# Vorlage_ATmega2560-16AU.net
KiCad netlist of a schematic drawn in EAGLE
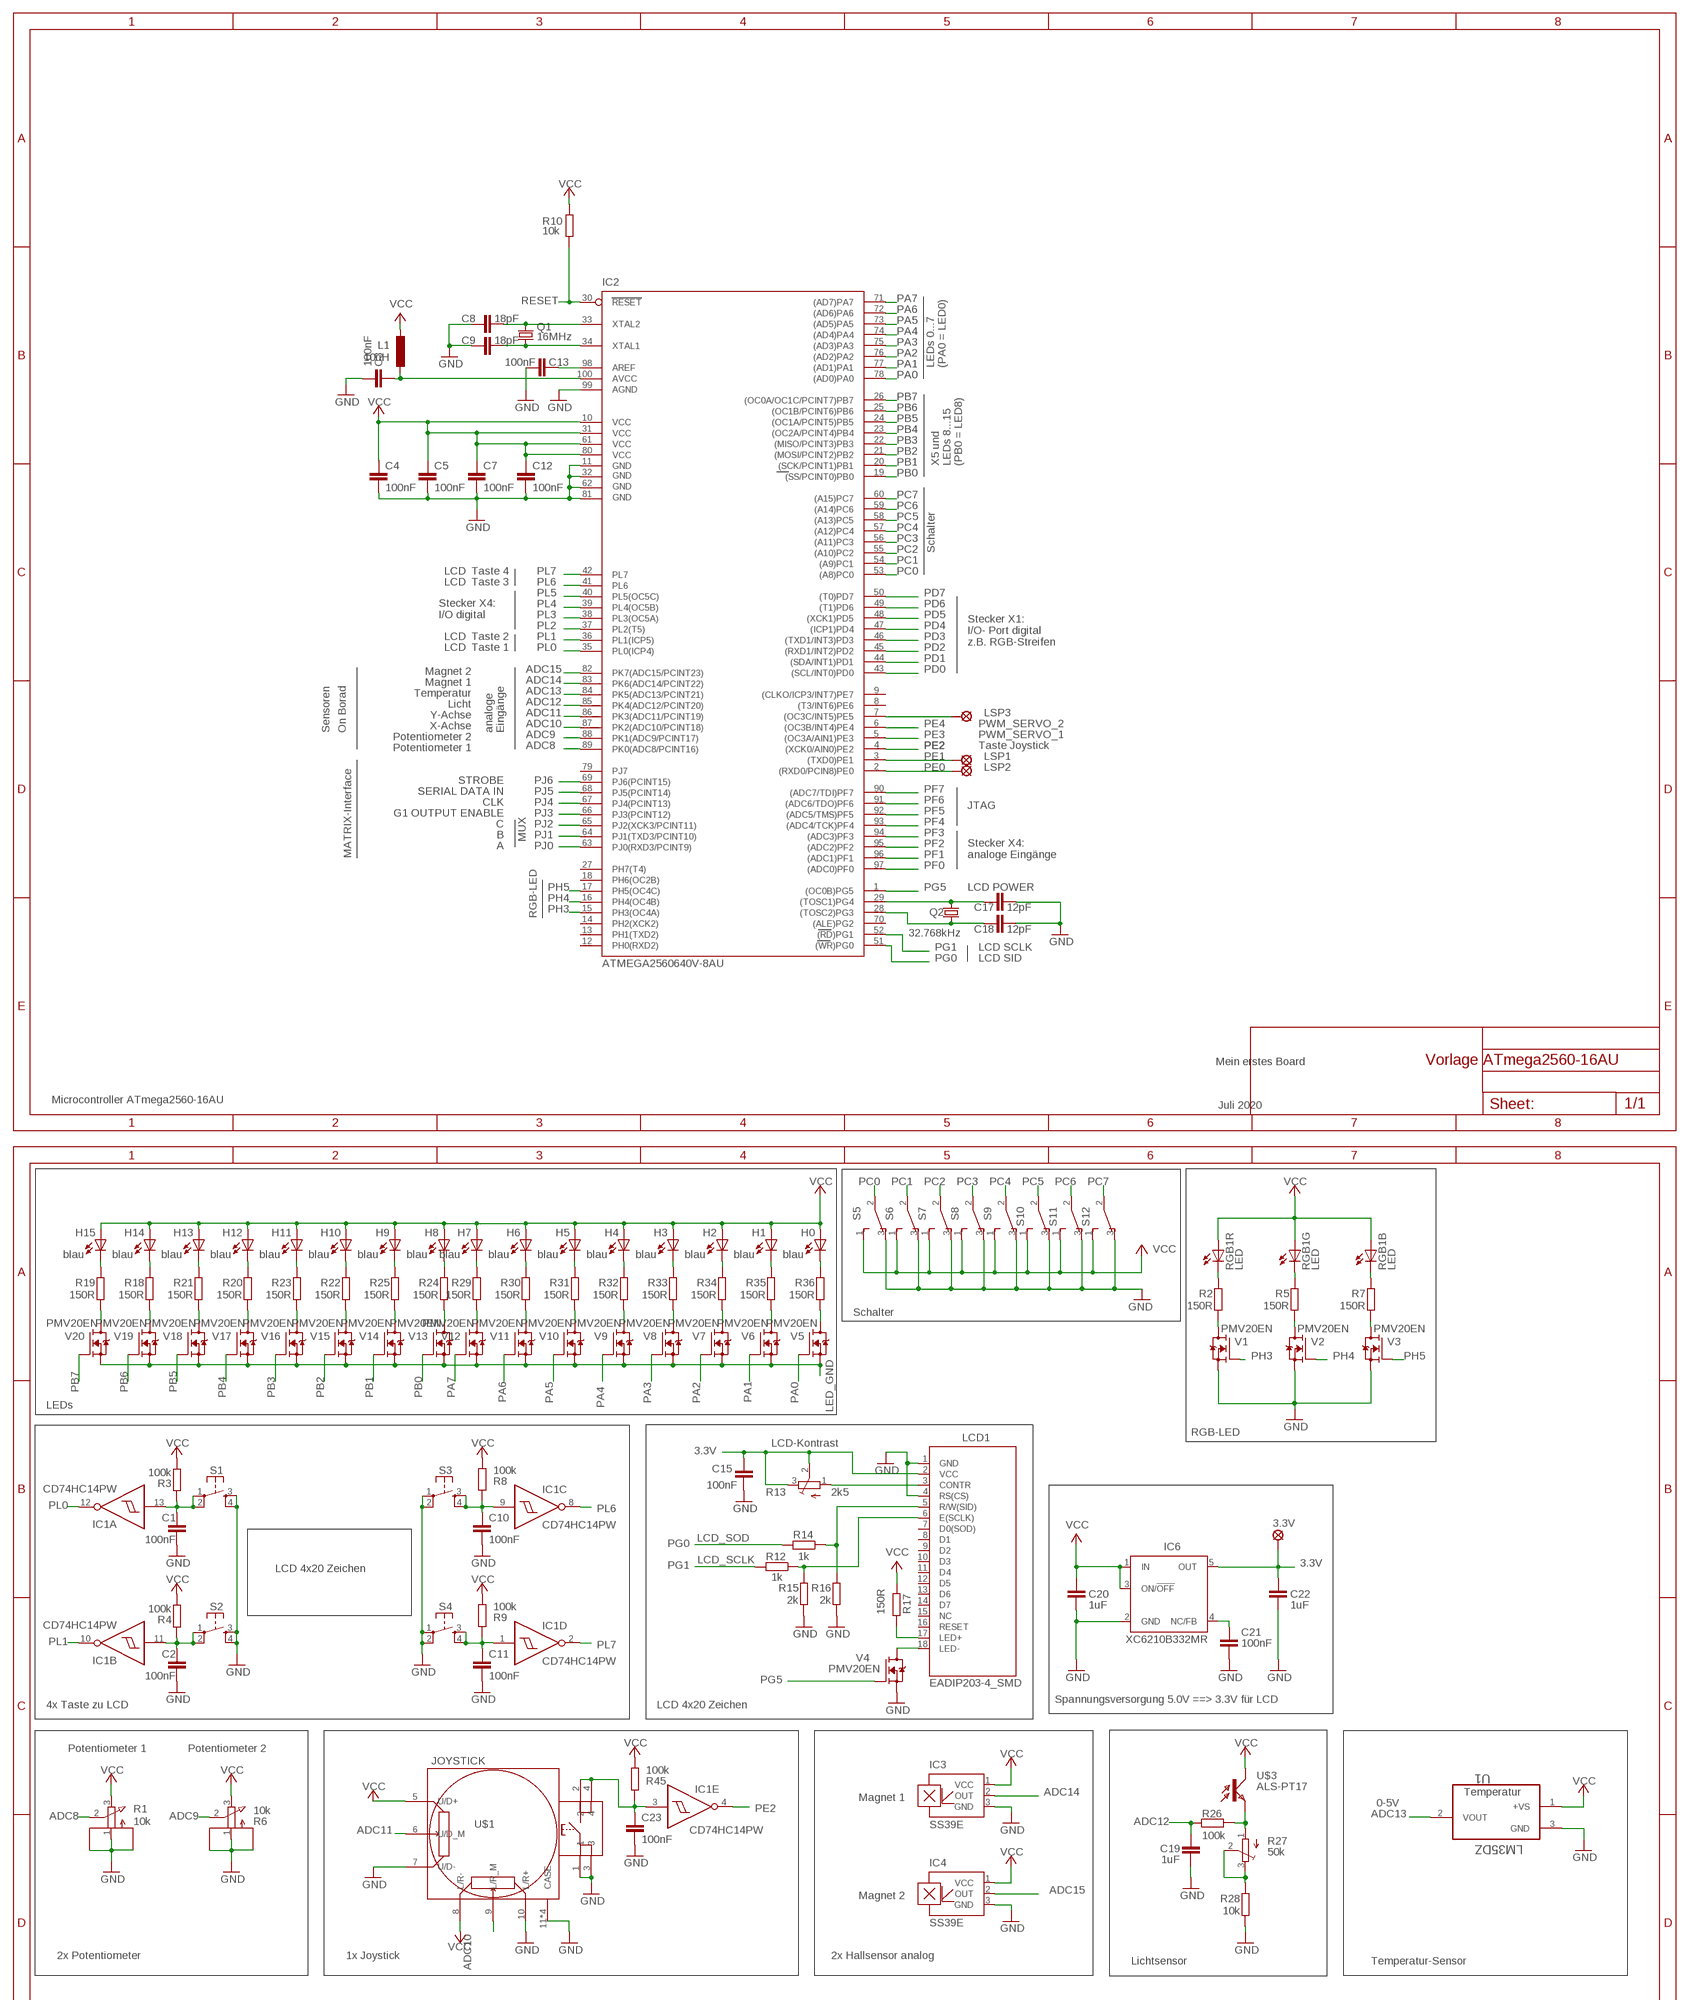
[diagram p0: schematic, sheet 1, part 1 of 2]
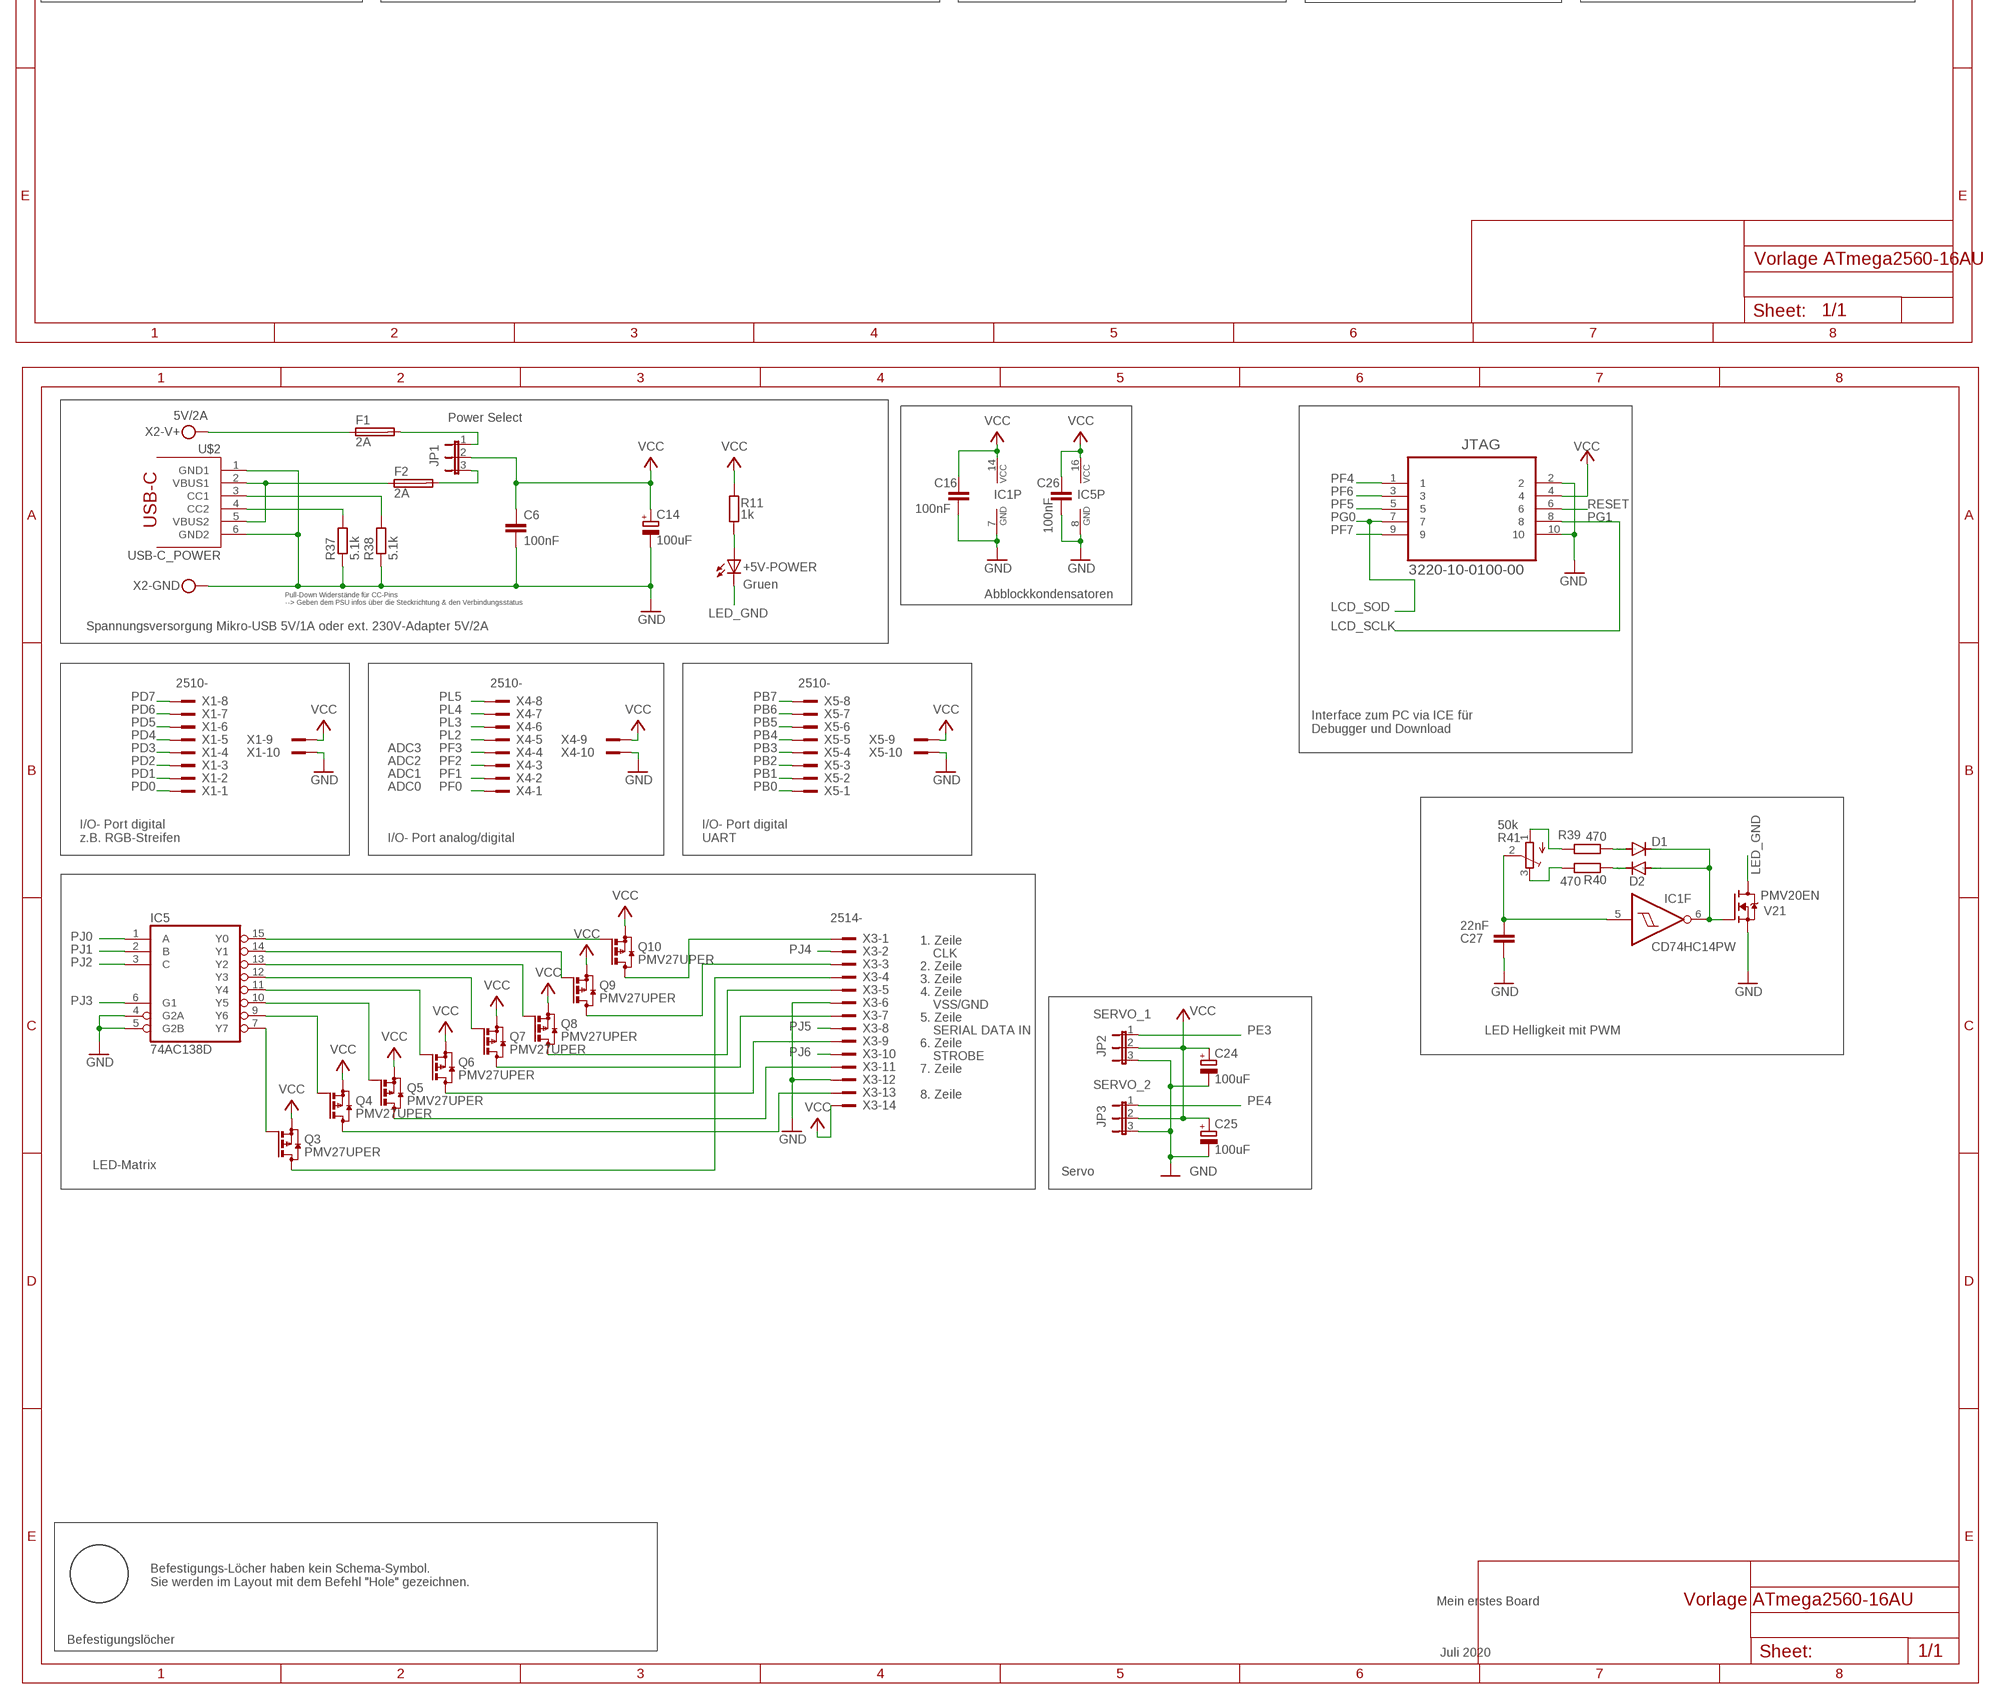
[diagram p1: schematic, sheet 1, part 2 of 2]

(export (version "E")
  (design (tool "Eeschema 10.0.6"))
  (components
    (comp (ref "+5V-POWER")
      (value "Gruen")
      (footprint "eagle-import:CHIPLED_1206")
      (libsource (lib "eagle-import") (part "LEDCHIPLED_1206"))
    )
    (comp (ref "3.3V")
      (value "3.3V")
      (footprint "eagle-import:LSP11")
      (libsource (lib "eagle-import") (part "LSP11"))
    )
    (comp (ref "C1")
      (value "100nF")
      (footprint "eagle-import:C1206")
      (libsource (lib "eagle-import") (part "C-EUC1206"))
    )
    (comp (ref "C2")
      (value "100nF")
      (footprint "eagle-import:C1206")
      (libsource (lib "eagle-import") (part "C-EUC1206"))
    )
    (comp (ref "C3")
      (value "100nF")
      (footprint "eagle-import:C1206")
      (libsource (lib "eagle-import") (part "C-EUC1206"))
    )
    (comp (ref "C4")
      (value "100nF")
      (footprint "eagle-import:C1206")
      (libsource (lib "eagle-import") (part "C-EUC1206"))
    )
    (comp (ref "C5")
      (value "100nF")
      (footprint "eagle-import:C1206")
      (libsource (lib "eagle-import") (part "C-EUC1206"))
    )
    (comp (ref "C6")
      (value "100nF")
      (footprint "eagle-import:C1206")
      (libsource (lib "eagle-import") (part "C-EUC1206"))
    )
    (comp (ref "C7")
      (value "100nF")
      (footprint "eagle-import:C1206")
      (libsource (lib "eagle-import") (part "C-EUC1206"))
    )
    (comp (ref "C8")
      (value "18pF")
      (footprint "eagle-import:C0805K")
      (libsource (lib "eagle-import") (part "C-EUC0805K"))
    )
    (comp (ref "C9")
      (value "18pF")
      (footprint "eagle-import:C0805K")
      (libsource (lib "eagle-import") (part "C-EUC0805K"))
    )
    (comp (ref "C10")
      (value "100nF")
      (footprint "eagle-import:C1206")
      (libsource (lib "eagle-import") (part "C-EUC1206"))
    )
    (comp (ref "C11")
      (value "100nF")
      (footprint "eagle-import:C1206")
      (libsource (lib "eagle-import") (part "C-EUC1206"))
    )
    (comp (ref "C12")
      (value "100nF")
      (footprint "eagle-import:C1206")
      (libsource (lib "eagle-import") (part "C-EUC1206"))
    )
    (comp (ref "C13")
      (value "100nF")
      (footprint "eagle-import:C1206")
      (libsource (lib "eagle-import") (part "C-EUC1206"))
    )
    (comp (ref "C14")
      (value "100uF")
      (footprint "eagle-import:UD-6,3X5,8_NICHICON")
      (libsource (lib "eagle-import") (part "CPOL-EUUD-6,3X8,8"))
    )
    (comp (ref "C15")
      (value "100nF")
      (footprint "eagle-import:C1206")
      (libsource (lib "eagle-import") (part "C-EUC1206"))
    )
    (comp (ref "C16")
      (value "100nF")
      (footprint "eagle-import:C1206")
      (libsource (lib "eagle-import") (part "C-EUC1206"))
    )
    (comp (ref "C17")
      (value "12pF")
      (footprint "eagle-import:C0805K")
      (libsource (lib "eagle-import") (part "C-EUC0805K"))
    )
    (comp (ref "C18")
      (value "12pF")
      (footprint "eagle-import:C0805K")
      (libsource (lib "eagle-import") (part "C-EUC0805K"))
    )
    (comp (ref "C19")
      (value "1uF")
      (footprint "eagle-import:C1206")
      (libsource (lib "eagle-import") (part "C-EUC1206"))
    )
    (comp (ref "C20")
      (value "1uF")
      (footprint "eagle-import:C1206")
      (libsource (lib "eagle-import") (part "C-EUC1206"))
    )
    (comp (ref "C21")
      (value "100nF")
      (footprint "eagle-import:C1206")
      (libsource (lib "eagle-import") (part "C-EUC1206"))
    )
    (comp (ref "C22")
      (value "1uF")
      (footprint "eagle-import:C1206")
      (libsource (lib "eagle-import") (part "C-EUC1206"))
    )
    (comp (ref "C23")
      (value "100nF")
      (footprint "eagle-import:C1206")
      (libsource (lib "eagle-import") (part "C-EUC1206"))
    )
    (comp (ref "C24")
      (value "100uF")
      (footprint "eagle-import:UD-6,3X5,8_NICHICON")
      (libsource (lib "eagle-import") (part "CPOL-EUUD-6,3X8,8"))
    )
    (comp (ref "C25")
      (value "100uF")
      (footprint "eagle-import:UD-6,3X5,8_NICHICON")
      (libsource (lib "eagle-import") (part "CPOL-EUUD-6,3X8,8"))
    )
    (comp (ref "C26")
      (value "100nF")
      (footprint "eagle-import:C1206")
      (libsource (lib "eagle-import") (part "C-EUC1206"))
    )
    (comp (ref "C27")
      (value "22nF")
      (footprint "eagle-import:C0805")
      (libsource (lib "eagle-import") (part "C-EUC0805"))
    )
    (comp (ref "D1")
      (value "DIODE-SOD123")
      (footprint "eagle-import:SOD123")
      (libsource (lib "eagle-import") (part "DIODE-SOD123"))
    )
    (comp (ref "D2")
      (value "DIODE-SOD123")
      (footprint "eagle-import:SOD123")
      (libsource (lib "eagle-import") (part "DIODE-SOD123"))
    )
    (comp (ref "F1")
      (value "2A")
      (footprint "eagle-import:F1206")
      (libsource (lib "eagle-import") (part "195601206"))
    )
    (comp (ref "F2")
      (value "2A")
      (footprint "eagle-import:F1206")
      (libsource (lib "eagle-import") (part "195601206"))
    )
    (comp (ref "H0")
      (value "blau")
      (footprint "eagle-import:CHIPLED_1206")
      (libsource (lib "eagle-import") (part "LEDCHIPLED_1206"))
    )
    (comp (ref "H1")
      (value "blau")
      (footprint "eagle-import:CHIPLED_1206")
      (libsource (lib "eagle-import") (part "LEDCHIPLED_1206"))
    )
    (comp (ref "H2")
      (value "blau")
      (footprint "eagle-import:CHIPLED_1206")
      (libsource (lib "eagle-import") (part "LEDCHIPLED_1206"))
    )
    (comp (ref "H3")
      (value "blau")
      (footprint "eagle-import:CHIPLED_1206")
      (libsource (lib "eagle-import") (part "LEDCHIPLED_1206"))
    )
    (comp (ref "H4")
      (value "blau")
      (footprint "eagle-import:CHIPLED_1206")
      (libsource (lib "eagle-import") (part "LEDCHIPLED_1206"))
    )
    (comp (ref "H5")
      (value "blau")
      (footprint "eagle-import:CHIPLED_1206")
      (libsource (lib "eagle-import") (part "LEDCHIPLED_1206"))
    )
    (comp (ref "H6")
      (value "blau")
      (footprint "eagle-import:CHIPLED_1206")
      (libsource (lib "eagle-import") (part "LEDCHIPLED_1206"))
    )
    (comp (ref "H7")
      (value "blau")
      (footprint "eagle-import:CHIPLED_1206")
      (libsource (lib "eagle-import") (part "LEDCHIPLED_1206"))
    )
    (comp (ref "H8")
      (value "blau")
      (footprint "eagle-import:CHIPLED_1206")
      (libsource (lib "eagle-import") (part "LEDCHIPLED_1206"))
    )
    (comp (ref "H9")
      (value "blau")
      (footprint "eagle-import:CHIPLED_1206")
      (libsource (lib "eagle-import") (part "LEDCHIPLED_1206"))
    )
    (comp (ref "H10")
      (value "blau")
      (footprint "eagle-import:CHIPLED_1206")
      (libsource (lib "eagle-import") (part "LEDCHIPLED_1206"))
    )
    (comp (ref "H11")
      (value "blau")
      (footprint "eagle-import:CHIPLED_1206")
      (libsource (lib "eagle-import") (part "LEDCHIPLED_1206"))
    )
    (comp (ref "H12")
      (value "blau")
      (footprint "eagle-import:CHIPLED_1206")
      (libsource (lib "eagle-import") (part "LEDCHIPLED_1206"))
    )
    (comp (ref "H13")
      (value "blau")
      (footprint "eagle-import:CHIPLED_1206")
      (libsource (lib "eagle-import") (part "LEDCHIPLED_1206"))
    )
    (comp (ref "H14")
      (value "blau")
      (footprint "eagle-import:CHIPLED_1206")
      (libsource (lib "eagle-import") (part "LEDCHIPLED_1206"))
    )
    (comp (ref "H15")
      (value "blau")
      (footprint "eagle-import:CHIPLED_1206")
      (libsource (lib "eagle-import") (part "LEDCHIPLED_1206"))
    )
    (comp (ref "IC1")
      (value "CD74HC14PW")
      (footprint "eagle-import:SO14")
      (libsource (lib "eagle-import") (part "7414D"))
    )
    (comp (ref "IC2")
      (value "ATMEGA2560640V-8AU")
      (footprint "eagle-import:TQFP100")
      (libsource (lib "eagle-import") (part "ATMEGA2560AU640V-8"))
    )
    (comp (ref "IC3")
      (value "SS39E")
      (footprint "eagle-import:SOT23-W")
      (fields (field (name "MF") "ALLEGRO MICROSYSTEMS, INC.") (field (name "MPN") "A1301ELHLT-T"))
      (libsource (lib "eagle-import") (part "A13?LH01"))
    )
    (comp (ref "IC4")
      (value "SS39E")
      (footprint "eagle-import:SOT23-W")
      (fields (field (name "MF") "ALLEGRO MICROSYSTEMS, INC.") (field (name "MPN") "A1301ELHLT-T"))
      (libsource (lib "eagle-import") (part "A13?LH01"))
    )
    (comp (ref "IC5")
      (value "74AC138D")
      (footprint "eagle-import:SO16")
      (libsource (lib "eagle-import") (part "74138DAC"))
    )
    (comp (ref "IC6")
      (value "XC6210B332MR")
      (footprint "eagle-import:SOT23-DBV")
      (libsource (lib "eagle-import") (part "LP2985-XXDBVR"))
    )
    (comp (ref "JP1")
      (value "Power Select")
      (footprint "eagle-import:JP2")
      (libsource (lib "eagle-import") (part "JP2E"))
    )
    (comp (ref "JP2")
      (value "SERVO_1")
      (footprint "eagle-import:JP2")
      (libsource (lib "eagle-import") (part "JP2E"))
    )
    (comp (ref "JP3")
      (value "SERVO_2")
      (footprint "eagle-import:JP2")
      (libsource (lib "eagle-import") (part "JP2E"))
    )
    (comp (ref "JTAG")
      (value "3220-10-0100-00")
      (footprint "eagle-import:SAMTEC_FTS-105-01-L-D")
      (fields (field (name "MPN") "FTS-105-01-L-D"))
      (libsource (lib "eagle-import") (part "FTS-105-01-L-D"))
    )
    (comp (ref "L1")
      (value "10uH")
      (footprint "eagle-import:L2825P")
      (libsource (lib "eagle-import") (part "L-EUL2825P"))
    )
    (comp (ref "LCD1")
      (value "EADIP203-4_SMD")
      (footprint "eagle-import:EADIP203-4SMD")
      (libsource (lib "eagle-import") (part "EADIP203-4EADIP203-4SMD"))
    )
    (comp (ref "LSP1")
      (value "LSP11")
      (footprint "eagle-import:LSP11")
      (libsource (lib "eagle-import") (part "LSP11"))
    )
    (comp (ref "LSP2")
      (value "LSP11")
      (footprint "eagle-import:LSP11")
      (libsource (lib "eagle-import") (part "LSP11"))
    )
    (comp (ref "LSP3")
      (value "LSP11")
      (footprint "eagle-import:LSP11")
      (libsource (lib "eagle-import") (part "LSP11"))
    )
    (comp (ref "Q1")
      (value "16MHz")
      (footprint "eagle-import:HC49UP")
      (libsource (lib "eagle-import") (part "CRYSTALHC49UP"))
    )
    (comp (ref "Q2")
      (value "32.768kHz")
      (footprint "eagle-import:TC38H")
      (libsource (lib "eagle-import") (part "CRYSTALTC38H"))
    )
    (comp (ref "Q3")
      (value "PMV27UPER")
      (footprint "eagle-import:SOT23")
      (libsource (lib "eagle-import") (part "BSS84"))
    )
    (comp (ref "Q4")
      (value "PMV27UPER")
      (footprint "eagle-import:SOT23")
      (libsource (lib "eagle-import") (part "BSS84"))
    )
    (comp (ref "Q5")
      (value "PMV27UPER")
      (footprint "eagle-import:SOT23")
      (libsource (lib "eagle-import") (part "BSS84"))
    )
    (comp (ref "Q6")
      (value "PMV27UPER")
      (footprint "eagle-import:SOT23")
      (libsource (lib "eagle-import") (part "BSS84"))
    )
    (comp (ref "Q7")
      (value "PMV27UPER")
      (footprint "eagle-import:SOT23")
      (libsource (lib "eagle-import") (part "BSS84"))
    )
    (comp (ref "Q8")
      (value "PMV27UPER")
      (footprint "eagle-import:SOT23")
      (libsource (lib "eagle-import") (part "BSS84"))
    )
    (comp (ref "Q9")
      (value "PMV27UPER")
      (footprint "eagle-import:SOT23")
      (libsource (lib "eagle-import") (part "BSS84"))
    )
    (comp (ref "Q10")
      (value "PMV27UPER")
      (footprint "eagle-import:SOT23")
      (libsource (lib "eagle-import") (part "BSS84"))
    )
    (comp (ref "R1")
      (value "10k")
      (footprint "eagle-import:EVUF")
      (libsource (lib "eagle-import") (part "EVUA"))
    )
    (comp (ref "R2")
      (value "150R")
      (footprint "eagle-import:R1206")
      (libsource (lib "eagle-import") (part "rcl_334_R-EU_R1206"))
    )
    (comp (ref "R3")
      (value "100k")
      (footprint "eagle-import:R1206")
      (libsource (lib "eagle-import") (part "rcl_334_R-EU_R1206"))
    )
    (comp (ref "R4")
      (value "100k")
      (footprint "eagle-import:R1206")
      (libsource (lib "eagle-import") (part "rcl_334_R-EU_R1206"))
    )
    (comp (ref "R5")
      (value "150R")
      (footprint "eagle-import:R1206")
      (libsource (lib "eagle-import") (part "rcl_334_R-EU_R1206"))
    )
    (comp (ref "R6")
      (value "10k")
      (footprint "eagle-import:EVUF")
      (libsource (lib "eagle-import") (part "EVUA"))
    )
    (comp (ref "R7")
      (value "150R")
      (footprint "eagle-import:R1206")
      (libsource (lib "eagle-import") (part "rcl_334_R-EU_R1206"))
    )
    (comp (ref "R8")
      (value "100k")
      (footprint "eagle-import:R1206")
      (libsource (lib "eagle-import") (part "rcl_334_R-EU_R1206"))
    )
    (comp (ref "R9")
      (value "100k")
      (footprint "eagle-import:R1206")
      (libsource (lib "eagle-import") (part "rcl_334_R-EU_R1206"))
    )
    (comp (ref "R10")
      (value "10k")
      (footprint "eagle-import:R1206")
      (libsource (lib "eagle-import") (part "rcl_334_R-EU_R1206"))
    )
    (comp (ref "R11")
      (value "1k")
      (footprint "eagle-import:R1206")
      (libsource (lib "eagle-import") (part "rcl_334_R-EU_R1206"))
    )
    (comp (ref "R12")
      (value "1k")
      (footprint "eagle-import:R1206")
      (libsource (lib "eagle-import") (part "rcl_334_R-EU_R1206"))
    )
    (comp (ref "R13")
      (value "2k5")
      (footprint "eagle-import:3223G")
      (libsource (lib "eagle-import") (part "TRIM_EU-3223G"))
    )
    (comp (ref "R14")
      (value "1k")
      (footprint "eagle-import:R1206")
      (libsource (lib "eagle-import") (part "rcl_334_R-EU_R1206"))
    )
    (comp (ref "R15")
      (value "2k")
      (footprint "eagle-import:R1206")
      (libsource (lib "eagle-import") (part "rcl_334_R-EU_R1206"))
    )
    (comp (ref "R16")
      (value "2k")
      (footprint "eagle-import:R1206")
      (libsource (lib "eagle-import") (part "rcl_334_R-EU_R1206"))
    )
    (comp (ref "R17")
      (value "150R")
      (footprint "eagle-import:R1206")
      (libsource (lib "eagle-import") (part "rcl_334_R-EU_R1206"))
    )
    (comp (ref "R18")
      (value "150R")
      (footprint "eagle-import:R1206")
      (libsource (lib "eagle-import") (part "rcl_334_R-EU_R1206"))
    )
    (comp (ref "R19")
      (value "150R")
      (footprint "eagle-import:R1206")
      (libsource (lib "eagle-import") (part "rcl_334_R-EU_R1206"))
    )
    (comp (ref "R20")
      (value "150R")
      (footprint "eagle-import:R1206")
      (libsource (lib "eagle-import") (part "rcl_334_R-EU_R1206"))
    )
    (comp (ref "R21")
      (value "150R")
      (footprint "eagle-import:R1206")
      (libsource (lib "eagle-import") (part "rcl_334_R-EU_R1206"))
    )
    (comp (ref "R22")
      (value "150R")
      (footprint "eagle-import:R1206")
      (libsource (lib "eagle-import") (part "rcl_334_R-EU_R1206"))
    )
    (comp (ref "R23")
      (value "150R")
      (footprint "eagle-import:R1206")
      (libsource (lib "eagle-import") (part "rcl_334_R-EU_R1206"))
    )
    (comp (ref "R24")
      (value "150R")
      (footprint "eagle-import:R1206")
      (libsource (lib "eagle-import") (part "rcl_334_R-EU_R1206"))
    )
    (comp (ref "R25")
      (value "150R")
      (footprint "eagle-import:R1206")
      (libsource (lib "eagle-import") (part "rcl_334_R-EU_R1206"))
    )
    (comp (ref "R26")
      (value "100k")
      (footprint "eagle-import:R1206")
      (libsource (lib "eagle-import") (part "rcl_334_R-EU_R1206"))
    )
    (comp (ref "R27")
      (value "50k")
      (footprint "eagle-import:3223G")
      (libsource (lib "eagle-import") (part "TRIM_EU-3223G"))
    )
    (comp (ref "R28")
      (value "10k")
      (footprint "eagle-import:R1206")
      (libsource (lib "eagle-import") (part "rcl_334_R-EU_R1206"))
    )
    (comp (ref "R29")
      (value "150R")
      (footprint "eagle-import:R1206")
      (libsource (lib "eagle-import") (part "rcl_334_R-EU_R1206"))
    )
    (comp (ref "R30")
      (value "150R")
      (footprint "eagle-import:R1206")
      (libsource (lib "eagle-import") (part "rcl_334_R-EU_R1206"))
    )
    (comp (ref "R31")
      (value "150R")
      (footprint "eagle-import:R1206")
      (libsource (lib "eagle-import") (part "rcl_334_R-EU_R1206"))
    )
    (comp (ref "R32")
      (value "150R")
      (footprint "eagle-import:R1206")
      (libsource (lib "eagle-import") (part "rcl_334_R-EU_R1206"))
    )
    (comp (ref "R33")
      (value "150R")
      (footprint "eagle-import:R1206")
      (libsource (lib "eagle-import") (part "rcl_334_R-EU_R1206"))
    )
    (comp (ref "R34")
      (value "150R")
      (footprint "eagle-import:R1206")
      (libsource (lib "eagle-import") (part "rcl_334_R-EU_R1206"))
    )
    (comp (ref "R35")
      (value "150R")
      (footprint "eagle-import:R1206")
      (libsource (lib "eagle-import") (part "rcl_334_R-EU_R1206"))
    )
    (comp (ref "R36")
      (value "150R")
      (footprint "eagle-import:R1206")
      (libsource (lib "eagle-import") (part "rcl_334_R-EU_R1206"))
    )
    (comp (ref "R37")
      (value "5.1k")
      (footprint "eagle-import:R0805")
      (libsource (lib "eagle-import") (part "R-EU_R0805"))
    )
    (comp (ref "R38")
      (value "5.1k")
      (footprint "eagle-import:R0805")
      (libsource (lib "eagle-import") (part "R-EU_R0805"))
    )
    (comp (ref "R39")
      (value "470")
      (footprint "eagle-import:R0805")
      (libsource (lib "eagle-import") (part "R-EU_R0805"))
    )
    (comp (ref "R40")
      (value "470")
      (footprint "eagle-import:R0805")
      (libsource (lib "eagle-import") (part "R-EU_R0805"))
    )
    (comp (ref "R41")
      (value "50k")
      (footprint "eagle-import:3223G")
      (libsource (lib "eagle-import") (part "TRIM_EU-3223G"))
    )
    (comp (ref "R45")
      (value "100k")
      (footprint "eagle-import:R1206")
      (libsource (lib "eagle-import") (part "rcl_334_R-EU_R1206"))
    )
    (comp (ref "RGB1")
      (value "LED")
      (footprint "eagle-import:LED_MIT_DIFUSOR")
      (libsource (lib "eagle-import") (part "GM5WA94310AMIT_DIFUSOR"))
    )
    (comp (ref "S1")
      (value "TS42_4PAD")
      (footprint "eagle-import:TS42_4PAD")
      (libsource (lib "eagle-import") (part "TS42_4PAD"))
    )
    (comp (ref "S2")
      (value "TS42_4PAD")
      (footprint "eagle-import:TS42_4PAD")
      (libsource (lib "eagle-import") (part "TS42_4PAD"))
    )
    (comp (ref "S3")
      (value "TS42_4PAD")
      (footprint "eagle-import:TS42_4PAD")
      (libsource (lib "eagle-import") (part "TS42_4PAD"))
    )
    (comp (ref "S4")
      (value "TS42_4PAD")
      (footprint "eagle-import:TS42_4PAD")
      (libsource (lib "eagle-import") (part "TS42_4PAD"))
    )
    (comp (ref "S5")
      (value "TL36POSPDT_5MM")
      (footprint "eagle-import:SPDT_5MM")
      (libsource (lib "eagle-import") (part "TL36POSPDT_5MM"))
    )
    (comp (ref "S6")
      (value "TL36POSPDT_5MM")
      (footprint "eagle-import:SPDT_5MM")
      (libsource (lib "eagle-import") (part "TL36POSPDT_5MM"))
    )
    (comp (ref "S7")
      (value "TL36POSPDT_5MM")
      (footprint "eagle-import:SPDT_5MM")
      (libsource (lib "eagle-import") (part "TL36POSPDT_5MM"))
    )
    (comp (ref "S8")
      (value "TL36POSPDT_5MM")
      (footprint "eagle-import:SPDT_5MM")
      (libsource (lib "eagle-import") (part "TL36POSPDT_5MM"))
    )
    (comp (ref "S9")
      (value "TL36POSPDT_5MM")
      (footprint "eagle-import:SPDT_5MM")
      (libsource (lib "eagle-import") (part "TL36POSPDT_5MM"))
    )
    (comp (ref "S10")
      (value "TL36POSPDT_5MM")
      (footprint "eagle-import:SPDT_5MM")
      (libsource (lib "eagle-import") (part "TL36POSPDT_5MM"))
    )
    (comp (ref "S11")
      (value "TL36POSPDT_5MM")
      (footprint "eagle-import:SPDT_5MM")
      (libsource (lib "eagle-import") (part "TL36POSPDT_5MM"))
    )
    (comp (ref "S12")
      (value "TL36POSPDT_5MM")
      (footprint "eagle-import:SPDT_5MM")
      (libsource (lib "eagle-import") (part "TL36POSPDT_5MM"))
    )
    (comp (ref "U$1")
      (value "JOYSTICK")
      (footprint "eagle-import:RKJXV1224005")
      (libsource (lib "eagle-import") (part "JOYSTICK"))
    )
    (comp (ref "U$2")
      (value "USB-C_POWER")
      (footprint "eagle-import:USB-C")
      (libsource (lib "eagle-import") (part "USB-C_POWER"))
    )
    (comp (ref "U$3")
      (value "ALS-PT17")
      (footprint "eagle-import:SOD232-W")
      (libsource (lib "eagle-import") (part "ALS-PT17-51C"))
    )
    (comp (ref "U1")
      (value "LM35DZ")
      (footprint "eagle-import:TO127P254X495-3P")
      (libsource (lib "eagle-import") (part "LM35DZ"))
    )
    (comp (ref "V1")
      (value "PMV20EN")
      (footprint "eagle-import:SOT23")
      (libsource (lib "eagle-import") (part "BSS138"))
    )
    (comp (ref "V2")
      (value "PMV20EN")
      (footprint "eagle-import:SOT23")
      (libsource (lib "eagle-import") (part "BSS138"))
    )
    (comp (ref "V3")
      (value "PMV20EN")
      (footprint "eagle-import:SOT23")
      (libsource (lib "eagle-import") (part "BSS138"))
    )
    (comp (ref "V4")
      (value "PMV20EN")
      (footprint "eagle-import:SOT23")
      (libsource (lib "eagle-import") (part "BSS138"))
    )
    (comp (ref "V5")
      (value "PMV20EN")
      (footprint "eagle-import:SOT23")
      (libsource (lib "eagle-import") (part "BSS138"))
    )
    (comp (ref "V6")
      (value "PMV20EN")
      (footprint "eagle-import:SOT23")
      (libsource (lib "eagle-import") (part "BSS138"))
    )
    (comp (ref "V7")
      (value "PMV20EN")
      (footprint "eagle-import:SOT23")
      (libsource (lib "eagle-import") (part "BSS138"))
    )
    (comp (ref "V8")
      (value "PMV20EN")
      (footprint "eagle-import:SOT23")
      (libsource (lib "eagle-import") (part "BSS138"))
    )
    (comp (ref "V9")
      (value "PMV20EN")
      (footprint "eagle-import:SOT23")
      (libsource (lib "eagle-import") (part "BSS138"))
    )
    (comp (ref "V10")
      (value "PMV20EN")
      (footprint "eagle-import:SOT23")
      (libsource (lib "eagle-import") (part "BSS138"))
    )
    (comp (ref "V11")
      (value "PMV20EN")
      (footprint "eagle-import:SOT23")
      (libsource (lib "eagle-import") (part "BSS138"))
    )
    (comp (ref "V12")
      (value "PMV20EN")
      (footprint "eagle-import:SOT23")
      (libsource (lib "eagle-import") (part "BSS138"))
    )
    (comp (ref "V13")
      (value "PMV20EN")
      (footprint "eagle-import:SOT23")
      (libsource (lib "eagle-import") (part "BSS138"))
    )
    (comp (ref "V14")
      (value "PMV20EN")
      (footprint "eagle-import:SOT23")
      (libsource (lib "eagle-import") (part "BSS138"))
    )
    (comp (ref "V15")
      (value "PMV20EN")
      (footprint "eagle-import:SOT23")
      (libsource (lib "eagle-import") (part "BSS138"))
    )
    (comp (ref "V16")
      (value "PMV20EN")
      (footprint "eagle-import:SOT23")
      (libsource (lib "eagle-import") (part "BSS138"))
    )
    (comp (ref "V17")
      (value "PMV20EN")
      (footprint "eagle-import:SOT23")
      (libsource (lib "eagle-import") (part "BSS138"))
    )
    (comp (ref "V18")
      (value "PMV20EN")
      (footprint "eagle-import:SOT23")
      (libsource (lib "eagle-import") (part "BSS138"))
    )
    (comp (ref "V19")
      (value "PMV20EN")
      (footprint "eagle-import:SOT23")
      (libsource (lib "eagle-import") (part "BSS138"))
    )
    (comp (ref "V20")
      (value "PMV20EN")
      (footprint "eagle-import:SOT23")
      (libsource (lib "eagle-import") (part "BSS138"))
    )
    (comp (ref "V21")
      (value "PMV20EN")
      (footprint "eagle-import:SOT23")
      (libsource (lib "eagle-import") (part "BSS138"))
    )
    (comp (ref "X1")
      (value "2510-")
      (footprint "eagle-import:PAK100_2500-10")
      (fields (field (name "MF") "3M") (field (name "MPN") "2510-6002UB"))
      (libsource (lib "eagle-import") (part "2510-"))
    )
    (comp (ref "X2")
      (value "+5V")
      (footprint "eagle-import:MKDSN1,5_2-5,08")
      (fields (field (name "MPN") "MKDSN 1,5/2-5.08"))
      (libsource (lib "eagle-import") (part "MKDSN1,5/2-5,08"))
    )
    (comp (ref "X3")
      (value "2514-")
      (footprint "eagle-import:PAK100_2500-14")
      (libsource (lib "eagle-import") (part "2514-"))
    )
    (comp (ref "X4")
      (value "2510-")
      (footprint "eagle-import:PAK100_2500-10")
      (fields (field (name "MF") "3M") (field (name "MPN") "2510-6002UB"))
      (libsource (lib "eagle-import") (part "2510-"))
    )
    (comp (ref "X5")
      (value "2510-")
      (footprint "eagle-import:PAK100_2500-10")
      (fields (field (name "MF") "3M") (field (name "MPN") "2510-6002UB"))
      (libsource (lib "eagle-import") (part "2510-"))
    )
  )
  (nets
    (net (code "1") (name "/3.3V") (class "Default")
      (node (ref "3.3V") (pin "MP") (pinfunction "MP_MP") (pintype "passive"))
      (node (ref "C15") (pin "1") (pinfunction "1_1") (pintype "passive"))
      (node (ref "C22") (pin "1") (pinfunction "1_1") (pintype "passive"))
      (node (ref "IC6") (pin "5") (pinfunction "OUT_5") (pintype "passive"))
      (node (ref "LCD1") (pin "2") (pinfunction "VCC_2") (pintype "passive"))
      (node (ref "R13") (pin "2") (pinfunction "S_2") (pintype "passive"))
      (node (ref "R13") (pin "3") (pinfunction "E_3") (pintype "passive"))
    )
    (net (code "2") (name "/ADC8") (class "Default")
      (node (ref "IC2") (pin "89") (pinfunction "PK0(ADC8/PCINT16)_89") (pintype "bidirectional"))
      (node (ref "R1") (pin "2") (pinfunction "S_2") (pintype "passive"))
    )
    (net (code "3") (name "/ADC9") (class "Default")
      (node (ref "IC2") (pin "88") (pinfunction "PK1(ADC9/PCINT17)_88") (pintype "bidirectional"))
      (node (ref "R6") (pin "2") (pinfunction "S_2") (pintype "passive"))
    )
    (net (code "4") (name "/ADC10") (class "Default")
      (node (ref "IC2") (pin "87") (pinfunction "PK2(ADC10/PCINT18)_87") (pintype "bidirectional"))
      (node (ref "U$1") (pin "9") (pinfunction "L/R_M_9") (pintype "bidirectional"))
    )
    (net (code "5") (name "/ADC11") (class "Default")
      (node (ref "IC2") (pin "86") (pinfunction "PK3(ADC11/PCINT19)_86") (pintype "bidirectional"))
      (node (ref "U$1") (pin "6") (pinfunction "U/D_M_6") (pintype "bidirectional"))
    )
    (net (code "6") (name "/ADC12") (class "Default")
      (node (ref "C19") (pin "2") (pinfunction "2_2") (pintype "passive"))
      (node (ref "IC2") (pin "85") (pinfunction "PK4(ADC12/PCINT20)_85") (pintype "bidirectional"))
      (node (ref "R26") (pin "1") (pinfunction "1_1") (pintype "passive"))
    )
    (net (code "7") (name "/ADC13") (class "Default")
      (node (ref "IC2") (pin "84") (pinfunction "PK5(ADC13/PCINT21)_84") (pintype "bidirectional"))
      (node (ref "U1") (pin "2") (pinfunction "VOUT_2") (pintype "output"))
    )
    (net (code "8") (name "/ADC14") (class "Default")
      (node (ref "IC2") (pin "83") (pinfunction "PK6(ADC14/PCINT22)_83") (pintype "bidirectional"))
      (node (ref "IC3") (pin "2") (pinfunction "OUT_2") (pintype "output"))
    )
    (net (code "9") (name "/ADC15") (class "Default")
      (node (ref "IC2") (pin "82") (pinfunction "PK7(ADC15/PCINT23)_82") (pintype "bidirectional"))
      (node (ref "IC4") (pin "2") (pinfunction "OUT_2") (pintype "output"))
    )
    (net (code "10") (name "/LED_GND") (class "Default")
      (node (ref "+5V-POWER") (pin "C") (pinfunction "C_C") (pintype "passive"))
      (node (ref "V10") (pin "2") (pinfunction "S_2") (pintype "passive"))
      (node (ref "V11") (pin "2") (pinfunction "S_2") (pintype "passive"))
      (node (ref "V12") (pin "2") (pinfunction "S_2") (pintype "passive"))
      (node (ref "V13") (pin "2") (pinfunction "S_2") (pintype "passive"))
      (node (ref "V14") (pin "2") (pinfunction "S_2") (pintype "passive"))
      (node (ref "V15") (pin "2") (pinfunction "S_2") (pintype "passive"))
      (node (ref "V16") (pin "2") (pinfunction "S_2") (pintype "passive"))
      (node (ref "V17") (pin "2") (pinfunction "S_2") (pintype "passive"))
      (node (ref "V18") (pin "2") (pinfunction "S_2") (pintype "passive"))
      (node (ref "V19") (pin "2") (pinfunction "S_2") (pintype "passive"))
      (node (ref "V20") (pin "2") (pinfunction "S_2") (pintype "passive"))
      (node (ref "V21") (pin "3") (pinfunction "D_3") (pintype "passive"))
      (node (ref "V5") (pin "2") (pinfunction "S_2") (pintype "passive"))
      (node (ref "V6") (pin "2") (pinfunction "S_2") (pintype "passive"))
      (node (ref "V7") (pin "2") (pinfunction "S_2") (pintype "passive"))
      (node (ref "V8") (pin "2") (pinfunction "S_2") (pintype "passive"))
      (node (ref "V9") (pin "2") (pinfunction "S_2") (pintype "passive"))
    )
    (net (code "11") (name "/PA0") (class "Default")
      (node (ref "IC2") (pin "78") (pinfunction "(AD0)PA0_78") (pintype "bidirectional"))
      (node (ref "V5") (pin "1") (pinfunction "G_1") (pintype "passive"))
    )
    (net (code "12") (name "/PA1") (class "Default")
      (node (ref "IC2") (pin "77") (pinfunction "(AD1)PA1_77") (pintype "bidirectional"))
      (node (ref "V6") (pin "1") (pinfunction "G_1") (pintype "passive"))
    )
    (net (code "13") (name "/PA2") (class "Default")
      (node (ref "IC2") (pin "76") (pinfunction "(AD2)PA2_76") (pintype "bidirectional"))
      (node (ref "V7") (pin "1") (pinfunction "G_1") (pintype "passive"))
    )
    (net (code "14") (name "/PA3") (class "Default")
      (node (ref "IC2") (pin "75") (pinfunction "(AD3)PA3_75") (pintype "bidirectional"))
      (node (ref "V8") (pin "1") (pinfunction "G_1") (pintype "passive"))
    )
    (net (code "15") (name "/PA4") (class "Default")
      (node (ref "IC2") (pin "74") (pinfunction "(AD4)PA4_74") (pintype "bidirectional"))
      (node (ref "V9") (pin "1") (pinfunction "G_1") (pintype "passive"))
    )
    (net (code "16") (name "/PA5") (class "Default")
      (node (ref "IC2") (pin "73") (pinfunction "(AD5)PA5_73") (pintype "bidirectional"))
      (node (ref "V10") (pin "1") (pinfunction "G_1") (pintype "passive"))
    )
    (net (code "17") (name "/PA6") (class "Default")
      (node (ref "IC2") (pin "72") (pinfunction "(AD6)PA6_72") (pintype "bidirectional"))
      (node (ref "V11") (pin "1") (pinfunction "G_1") (pintype "passive"))
    )
    (net (code "18") (name "/PA7") (class "Default")
      (node (ref "IC2") (pin "71") (pinfunction "(AD7)PA7_71") (pintype "bidirectional"))
      (node (ref "V12") (pin "1") (pinfunction "G_1") (pintype "passive"))
    )
    (net (code "19") (name "/PB0") (class "Default")
      (node (ref "IC2") (pin "19") (pinfunction "(SS/PCINT0)PB0_19") (pintype "bidirectional"))
      (node (ref "V13") (pin "1") (pinfunction "G_1") (pintype "passive"))
      (node (ref "X5") (pin "1") (pinfunction "KL_1") (pintype "passive"))
    )
    (net (code "20") (name "/PB1") (class "Default")
      (node (ref "IC2") (pin "20") (pinfunction "(SCK/PCINT1)PB1_20") (pintype "bidirectional"))
      (node (ref "V14") (pin "1") (pinfunction "G_1") (pintype "passive"))
      (node (ref "X5") (pin "2") (pinfunction "KL_2") (pintype "passive"))
    )
    (net (code "21") (name "/PB2") (class "Default")
      (node (ref "IC2") (pin "21") (pinfunction "(MOSI/PCINT2)PB2_21") (pintype "bidirectional"))
      (node (ref "V15") (pin "1") (pinfunction "G_1") (pintype "passive"))
      (node (ref "X5") (pin "3") (pinfunction "KL_3") (pintype "passive"))
    )
    (net (code "22") (name "/PB3") (class "Default")
      (node (ref "IC2") (pin "22") (pinfunction "(MISO/PCINT3)PB3_22") (pintype "bidirectional"))
      (node (ref "V16") (pin "1") (pinfunction "G_1") (pintype "passive"))
      (node (ref "X5") (pin "4") (pinfunction "KL_4") (pintype "passive"))
    )
    (net (code "23") (name "/PB4") (class "Default")
      (node (ref "IC2") (pin "23") (pinfunction "(OC2A/PCINT4)PB4_23") (pintype "bidirectional"))
      (node (ref "V17") (pin "1") (pinfunction "G_1") (pintype "passive"))
      (node (ref "X5") (pin "5") (pinfunction "KL_5") (pintype "passive"))
    )
    (net (code "24") (name "/PB5") (class "Default")
      (node (ref "IC2") (pin "24") (pinfunction "(OC1A/PCINT5)PB5_24") (pintype "bidirectional"))
      (node (ref "V18") (pin "1") (pinfunction "G_1") (pintype "passive"))
      (node (ref "X5") (pin "6") (pinfunction "KL_6") (pintype "passive"))
    )
    (net (code "25") (name "/PB6") (class "Default")
      (node (ref "IC2") (pin "25") (pinfunction "(OC1B/PCINT6)PB6_25") (pintype "bidirectional"))
      (node (ref "V19") (pin "1") (pinfunction "G_1") (pintype "passive"))
      (node (ref "X5") (pin "7") (pinfunction "KL_7") (pintype "passive"))
    )
    (net (code "26") (name "/PB7") (class "Default")
      (node (ref "IC2") (pin "26") (pinfunction "(OC0A/OC1C/PCINT7)PB7_26") (pintype "bidirectional"))
      (node (ref "V20") (pin "1") (pinfunction "G_1") (pintype "passive"))
      (node (ref "X5") (pin "8") (pinfunction "KL_8") (pintype "passive"))
    )
    (net (code "27") (name "/PC0") (class "Default")
      (node (ref "IC2") (pin "53") (pinfunction "(A8)PC0_53") (pintype "bidirectional"))
      (node (ref "S5") (pin "2") (pinfunction "P_2") (pintype "passive"))
    )
    (net (code "28") (name "/PC1") (class "Default")
      (node (ref "IC2") (pin "54") (pinfunction "(A9)PC1_54") (pintype "bidirectional"))
      (node (ref "S6") (pin "2") (pinfunction "P_2") (pintype "passive"))
    )
    (net (code "29") (name "/PC2") (class "Default")
      (node (ref "IC2") (pin "55") (pinfunction "(A10)PC2_55") (pintype "bidirectional"))
      (node (ref "S7") (pin "2") (pinfunction "P_2") (pintype "passive"))
    )
    (net (code "30") (name "/PC3") (class "Default")
      (node (ref "IC2") (pin "56") (pinfunction "(A11)PC3_56") (pintype "bidirectional"))
      (node (ref "S8") (pin "2") (pinfunction "P_2") (pintype "passive"))
    )
    (net (code "31") (name "/PC4") (class "Default")
      (node (ref "IC2") (pin "57") (pinfunction "(A12)PC4_57") (pintype "bidirectional"))
      (node (ref "S9") (pin "2") (pinfunction "P_2") (pintype "passive"))
    )
    (net (code "32") (name "/PC5") (class "Default")
      (node (ref "IC2") (pin "58") (pinfunction "(A13)PC5_58") (pintype "bidirectional"))
      (node (ref "S10") (pin "2") (pinfunction "P_2") (pintype "passive"))
    )
    (net (code "33") (name "/PC6") (class "Default")
      (node (ref "IC2") (pin "59") (pinfunction "(A14)PC6_59") (pintype "bidirectional"))
      (node (ref "S11") (pin "2") (pinfunction "P_2") (pintype "passive"))
    )
    (net (code "34") (name "/PC7") (class "Default")
      (node (ref "IC2") (pin "60") (pinfunction "(A15)PC7_60") (pintype "bidirectional"))
      (node (ref "S12") (pin "2") (pinfunction "P_2") (pintype "passive"))
    )
    (net (code "35") (name "/PD0") (class "Default")
      (node (ref "IC2") (pin "43") (pinfunction "(SCL/INT0)PD0_43") (pintype "bidirectional"))
      (node (ref "X1") (pin "1") (pinfunction "KL_1") (pintype "passive"))
    )
    (net (code "36") (name "/PD1") (class "Default")
      (node (ref "IC2") (pin "44") (pinfunction "(SDA/INT1)PD1_44") (pintype "bidirectional"))
      (node (ref "X1") (pin "2") (pinfunction "KL_2") (pintype "passive"))
    )
    (net (code "37") (name "/PD2") (class "Default")
      (node (ref "IC2") (pin "45") (pinfunction "(RXD1/INT2)PD2_45") (pintype "bidirectional"))
      (node (ref "X1") (pin "3") (pinfunction "KL_3") (pintype "passive"))
    )
    (net (code "38") (name "/PD3") (class "Default")
      (node (ref "IC2") (pin "46") (pinfunction "(TXD1/INT3)PD3_46") (pintype "bidirectional"))
      (node (ref "X1") (pin "4") (pinfunction "KL_4") (pintype "passive"))
    )
    (net (code "39") (name "/PD4") (class "Default")
      (node (ref "IC2") (pin "47") (pinfunction "(ICP1)PD4_47") (pintype "bidirectional"))
      (node (ref "X1") (pin "5") (pinfunction "KL_5") (pintype "passive"))
    )
    (net (code "40") (name "/PD5") (class "Default")
      (node (ref "IC2") (pin "48") (pinfunction "(XCK1)PD5_48") (pintype "bidirectional"))
      (node (ref "X1") (pin "6") (pinfunction "KL_6") (pintype "passive"))
    )
    (net (code "41") (name "/PD6") (class "Default")
      (node (ref "IC2") (pin "49") (pinfunction "(T1)PD6_49") (pintype "bidirectional"))
      (node (ref "X1") (pin "7") (pinfunction "KL_7") (pintype "passive"))
    )
    (net (code "42") (name "/PD7") (class "Default")
      (node (ref "IC2") (pin "50") (pinfunction "(T0)PD7_50") (pintype "bidirectional"))
      (node (ref "X1") (pin "8") (pinfunction "KL_8") (pintype "passive"))
    )
    (net (code "43") (name "/PE0") (class "Default")
      (node (ref "IC2") (pin "2") (pinfunction "(RXD0/PCIN8)PE0_2") (pintype "bidirectional"))
      (node (ref "LSP2") (pin "MP") (pinfunction "MP_MP") (pintype "passive"))
    )
    (net (code "44") (name "/PE1") (class "Default")
      (node (ref "IC2") (pin "3") (pinfunction "(TXD0)PE1_3") (pintype "bidirectional"))
      (node (ref "LSP1") (pin "MP") (pinfunction "MP_MP") (pintype "passive"))
    )
    (net (code "45") (name "/PE2") (class "Default")
      (node (ref "IC1") (pin "4") (pinfunction "O_4") (pintype "output"))
      (node (ref "IC2") (pin "4") (pinfunction "(XCK0/AIN0)PE2_4") (pintype "bidirectional"))
    )
    (net (code "46") (name "/PE3") (class "Default")
      (node (ref "IC2") (pin "5") (pinfunction "(OC3A/AIN1)PE3_5") (pintype "bidirectional"))
      (node (ref "JP2") (pin "1") (pinfunction "1_1") (pintype "passive"))
    )
    (net (code "47") (name "/PE4") (class "Default")
      (node (ref "IC2") (pin "6") (pinfunction "(OC3B/INT4)PE4_6") (pintype "bidirectional"))
      (node (ref "JP3") (pin "1") (pinfunction "1_1") (pintype "passive"))
    )
    (net (code "48") (name "/PF0") (class "Default")
      (node (ref "IC2") (pin "97") (pinfunction "(ADC0)PF0_97") (pintype "bidirectional"))
      (node (ref "X4") (pin "1") (pinfunction "KL_1") (pintype "passive"))
    )
    (net (code "49") (name "/PF1") (class "Default")
      (node (ref "IC2") (pin "96") (pinfunction "(ADC1)PF1_96") (pintype "bidirectional"))
      (node (ref "X4") (pin "2") (pinfunction "KL_2") (pintype "passive"))
    )
    (net (code "50") (name "/PF2") (class "Default")
      (node (ref "IC2") (pin "95") (pinfunction "(ADC2)PF2_95") (pintype "bidirectional"))
      (node (ref "X4") (pin "3") (pinfunction "KL_3") (pintype "passive"))
    )
    (net (code "51") (name "/PF3") (class "Default")
      (node (ref "IC2") (pin "94") (pinfunction "(ADC3)PF3_94") (pintype "bidirectional"))
      (node (ref "X4") (pin "4") (pinfunction "KL_4") (pintype "passive"))
    )
    (net (code "52") (name "/PF4") (class "Default")
      (node (ref "IC2") (pin "93") (pinfunction "(ADC4/TCK)PF4_93") (pintype "bidirectional"))
      (node (ref "JTAG") (pin "1") (pinfunction "1_1") (pintype "passive"))
    )
    (net (code "53") (name "/PF5") (class "Default")
      (node (ref "IC2") (pin "92") (pinfunction "(ADC5/TMS)PF5_92") (pintype "bidirectional"))
      (node (ref "JTAG") (pin "5") (pinfunction "5_5") (pintype "passive"))
    )
    (net (code "54") (name "/PF6") (class "Default")
      (node (ref "IC2") (pin "91") (pinfunction "(ADC6/TDO)PF6_91") (pintype "bidirectional"))
      (node (ref "JTAG") (pin "3") (pinfunction "3_3") (pintype "passive"))
    )
    (net (code "55") (name "/PF7") (class "Default")
      (node (ref "IC2") (pin "90") (pinfunction "(ADC7/TDI)PF7_90") (pintype "bidirectional"))
      (node (ref "JTAG") (pin "9") (pinfunction "9_9") (pintype "passive"))
    )
    (net (code "56") (name "/PG0") (class "Default")
      (node (ref "IC2") (pin "51") (pinfunction "(WR)PG0_51") (pintype "bidirectional"))
      (node (ref "JTAG") (pin "7") (pinfunction "7_7") (pintype "passive"))
      (node (ref "R14") (pin "2") (pinfunction "2_2") (pintype "passive"))
    )
    (net (code "57") (name "/PG1") (class "Default")
      (node (ref "IC2") (pin "52") (pinfunction "(RD)PG1_52") (pintype "bidirectional"))
      (node (ref "JTAG") (pin "8") (pinfunction "8_8") (pintype "passive"))
      (node (ref "R12") (pin "2") (pinfunction "2_2") (pintype "passive"))
    )
    (net (code "58") (name "/PG5") (class "Default")
      (node (ref "IC2") (pin "1") (pinfunction "(OC0B)PG5_1") (pintype "bidirectional"))
      (node (ref "V4") (pin "1") (pinfunction "G_1") (pintype "passive"))
    )
    (net (code "59") (name "/PH3") (class "Default")
      (node (ref "IC2") (pin "15") (pinfunction "PH3(OC4A)_15") (pintype "bidirectional"))
      (node (ref "V1") (pin "1") (pinfunction "G_1") (pintype "passive"))
    )
    (net (code "60") (name "/PH4") (class "Default")
      (node (ref "IC2") (pin "16") (pinfunction "PH4(OC4B)_16") (pintype "bidirectional"))
      (node (ref "V2") (pin "1") (pinfunction "G_1") (pintype "passive"))
    )
    (net (code "61") (name "/PH5") (class "Default")
      (node (ref "IC2") (pin "17") (pinfunction "PH5(OC4C)_17") (pintype "bidirectional"))
      (node (ref "V3") (pin "1") (pinfunction "G_1") (pintype "passive"))
    )
    (net (code "62") (name "/PJ0") (class "Default")
      (node (ref "IC2") (pin "63") (pinfunction "PJ0(RXD3/PCINT9)_63") (pintype "bidirectional"))
      (node (ref "IC5") (pin "1") (pinfunction "A_1") (pintype "input"))
    )
    (net (code "63") (name "/PJ1") (class "Default")
      (node (ref "IC2") (pin "64") (pinfunction "PJ1(TXD3/PCINT10)_64") (pintype "bidirectional"))
      (node (ref "IC5") (pin "2") (pinfunction "B_2") (pintype "input"))
    )
    (net (code "64") (name "/PJ2") (class "Default")
      (node (ref "IC2") (pin "65") (pinfunction "PJ2(XCK3/PCINT11)_65") (pintype "bidirectional"))
      (node (ref "IC5") (pin "3") (pinfunction "C_3") (pintype "input"))
    )
    (net (code "65") (name "/PJ3") (class "Default")
      (node (ref "IC2") (pin "66") (pinfunction "PJ3(PCINT12)_66") (pintype "bidirectional"))
      (node (ref "IC5") (pin "6") (pinfunction "G1_6") (pintype "input"))
    )
    (net (code "66") (name "/PJ4") (class "Default")
      (node (ref "IC2") (pin "67") (pinfunction "PJ4(PCINT13)_67") (pintype "bidirectional"))
      (node (ref "X3") (pin "2") (pinfunction "KL_2") (pintype "passive"))
    )
    (net (code "67") (name "/PJ5") (class "Default")
      (node (ref "IC2") (pin "68") (pinfunction "PJ5(PCINT14)_68") (pintype "bidirectional"))
      (node (ref "X3") (pin "8") (pinfunction "KL_8") (pintype "passive"))
    )
    (net (code "68") (name "/PJ6") (class "Default")
      (node (ref "IC2") (pin "69") (pinfunction "PJ6(PCINT15)_69") (pintype "bidirectional"))
      (node (ref "X3") (pin "10") (pinfunction "KL_10") (pintype "passive"))
    )
    (net (code "69") (name "/PL0") (class "Default")
      (node (ref "IC1") (pin "12") (pinfunction "O_12") (pintype "output"))
      (node (ref "IC2") (pin "35") (pinfunction "PL0(ICP4)_35") (pintype "bidirectional"))
    )
    (net (code "70") (name "/PL1") (class "Default")
      (node (ref "IC1") (pin "10") (pinfunction "O_10") (pintype "output"))
      (node (ref "IC2") (pin "36") (pinfunction "PL1(ICP5)_36") (pintype "bidirectional"))
    )
    (net (code "71") (name "/PL2") (class "Default")
      (node (ref "IC2") (pin "37") (pinfunction "PL2(T5)_37") (pintype "bidirectional"))
      (node (ref "X4") (pin "5") (pinfunction "KL_5") (pintype "passive"))
    )
    (net (code "72") (name "/PL3") (class "Default")
      (node (ref "IC2") (pin "38") (pinfunction "PL3(OC5A)_38") (pintype "bidirectional"))
      (node (ref "X4") (pin "6") (pinfunction "KL_6") (pintype "passive"))
    )
    (net (code "73") (name "/PL4") (class "Default")
      (node (ref "IC2") (pin "39") (pinfunction "PL4(OC5B)_39") (pintype "bidirectional"))
      (node (ref "X4") (pin "7") (pinfunction "KL_7") (pintype "passive"))
    )
    (net (code "74") (name "/PL5") (class "Default")
      (node (ref "IC2") (pin "40") (pinfunction "PL5(OC5C)_40") (pintype "bidirectional"))
      (node (ref "X4") (pin "8") (pinfunction "KL_8") (pintype "passive"))
    )
    (net (code "75") (name "/PL6") (class "Default")
      (node (ref "IC1") (pin "8") (pinfunction "O_8") (pintype "output"))
      (node (ref "IC2") (pin "41") (pinfunction "PL6_41") (pintype "bidirectional"))
    )
    (net (code "76") (name "/PL7") (class "Default")
      (node (ref "IC1") (pin "2") (pinfunction "O_2") (pintype "output"))
      (node (ref "IC2") (pin "42") (pinfunction "PL7_42") (pintype "bidirectional"))
    )
    (net (code "77") (name "/RESET") (class "Default")
      (node (ref "IC2") (pin "30") (pinfunction "RESET_30") (pintype "input"))
      (node (ref "JTAG") (pin "6") (pinfunction "6_6") (pintype "passive"))
      (node (ref "R10") (pin "1") (pinfunction "1_1") (pintype "passive"))
    )
    (net (code "78") (name "GND") (class "Default")
      (node (ref "C1") (pin "2") (pinfunction "2_2") (pintype "passive"))
      (node (ref "C10") (pin "2") (pinfunction "2_2") (pintype "passive"))
      (node (ref "C11") (pin "2") (pinfunction "2_2") (pintype "passive"))
      (node (ref "C12") (pin "2") (pinfunction "2_2") (pintype "passive"))
      (node (ref "C13") (pin "1") (pinfunction "1_1") (pintype "passive"))
      (node (ref "C14") (pin "-") (pinfunction "-_-") (pintype "passive"))
      (node (ref "C15") (pin "2") (pinfunction "2_2") (pintype "passive"))
      (node (ref "C16") (pin "2") (pinfunction "2_2") (pintype "passive"))
      (node (ref "C17") (pin "2") (pinfunction "2_2") (pintype "passive"))
      (node (ref "C18") (pin "2") (pinfunction "2_2") (pintype "passive"))
      (node (ref "C19") (pin "1") (pinfunction "1_1") (pintype "passive"))
      (node (ref "C2") (pin "2") (pinfunction "2_2") (pintype "passive"))
      (node (ref "C20") (pin "2") (pinfunction "2_2") (pintype "passive"))
      (node (ref "C21") (pin "2") (pinfunction "2_2") (pintype "passive"))
      (node (ref "C22") (pin "2") (pinfunction "2_2") (pintype "passive"))
      (node (ref "C23") (pin "2") (pinfunction "2_2") (pintype "passive"))
      (node (ref "C24") (pin "-") (pinfunction "-_-") (pintype "passive"))
      (node (ref "C25") (pin "-") (pinfunction "-_-") (pintype "passive"))
      (node (ref "C26") (pin "2") (pinfunction "2_2") (pintype "passive"))
      (node (ref "C27") (pin "2") (pinfunction "2_2") (pintype "passive"))
      (node (ref "C3") (pin "1") (pinfunction "1_1") (pintype "passive"))
      (node (ref "C4") (pin "2") (pinfunction "2_2") (pintype "passive"))
      (node (ref "C5") (pin "2") (pinfunction "2_2") (pintype "passive"))
      (node (ref "C6") (pin "2") (pinfunction "2_2") (pintype "passive"))
      (node (ref "C7") (pin "2") (pinfunction "2_2") (pintype "passive"))
      (node (ref "C8") (pin "1") (pinfunction "1_1") (pintype "passive"))
      (node (ref "C9") (pin "2") (pinfunction "2_2") (pintype "passive"))
      (node (ref "IC1") (pin "7") (pinfunction "GND_7") (pintype "power_in"))
      (node (ref "IC2") (pin "11") (pinfunction "GND_11") (pintype "power_in"))
      (node (ref "IC2") (pin "32") (pinfunction "GND1_32") (pintype "power_in"))
      (node (ref "IC2") (pin "62") (pinfunction "GND2_62") (pintype "power_in"))
      (node (ref "IC2") (pin "81") (pinfunction "GND3_81") (pintype "power_in"))
      (node (ref "IC2") (pin "99") (pinfunction "AGND_99") (pintype "power_in"))
      (node (ref "IC3") (pin "3") (pinfunction "GND_3") (pintype "power_in"))
      (node (ref "IC4") (pin "3") (pinfunction "GND_3") (pintype "power_in"))
      (node (ref "IC5") (pin "4") (pinfunction "G2A_4") (pintype "input"))
      (node (ref "IC5") (pin "5") (pinfunction "G2B_5") (pintype "input"))
      (node (ref "IC5") (pin "8") (pinfunction "GND_8") (pintype "power_in"))
      (node (ref "IC6") (pin "2") (pinfunction "GND_2") (pintype "power_in"))
      (node (ref "JP2") (pin "3") (pinfunction "3_3") (pintype "passive"))
      (node (ref "JP3") (pin "3") (pinfunction "3_3") (pintype "passive"))
      (node (ref "JTAG") (pin "10") (pinfunction "10_10") (pintype "passive"))
      (node (ref "JTAG") (pin "2") (pinfunction "2_2") (pintype "passive"))
      (node (ref "LCD1") (pin "1") (pinfunction "GND_1") (pintype "power_in"))
      (node (ref "LCD1") (pin "4") (pinfunction "RS(CS)_4") (pintype "input"))
      (node (ref "R1") (pin "1") (pinfunction "A_1") (pintype "passive"))
      (node (ref "R1") (pin "M1") (pinfunction "P$1_M1") (pintype "bidirectional"))
      (node (ref "R1") (pin "M2") (pinfunction "P$2_M2") (pintype "bidirectional"))
      (node (ref "R15") (pin "1") (pinfunction "1_1") (pintype "passive"))
      (node (ref "R16") (pin "1") (pinfunction "1_1") (pintype "passive"))
      (node (ref "R28") (pin "1") (pinfunction "1_1") (pintype "passive"))
      (node (ref "R37") (pin "1") (pinfunction "1_1") (pintype "passive"))
      (node (ref "R38") (pin "1") (pinfunction "1_1") (pintype "passive"))
      (node (ref "R6") (pin "1") (pinfunction "A_1") (pintype "passive"))
      (node (ref "R6") (pin "M1") (pinfunction "P$1_M1") (pintype "bidirectional"))
      (node (ref "R6") (pin "M2") (pinfunction "P$2_M2") (pintype "bidirectional"))
      (node (ref "S1") (pin "3") (pinfunction "3_3") (pintype "passive"))
      (node (ref "S1") (pin "4") (pinfunction "4_4") (pintype "passive"))
      (node (ref "S10") (pin "3") (pinfunction "O_3") (pintype "passive"))
      (node (ref "S11") (pin "3") (pinfunction "O_3") (pintype "passive"))
      (node (ref "S12") (pin "3") (pinfunction "O_3") (pintype "passive"))
      (node (ref "S2") (pin "3") (pinfunction "3_3") (pintype "passive"))
      (node (ref "S2") (pin "4") (pinfunction "4_4") (pintype "passive"))
      (node (ref "S3") (pin "1") (pinfunction "1_1") (pintype "passive"))
      (node (ref "S3") (pin "2") (pinfunction "2_2") (pintype "passive"))
      (node (ref "S4") (pin "1") (pinfunction "1_1") (pintype "passive"))
      (node (ref "S4") (pin "2") (pinfunction "2_2") (pintype "passive"))
      (node (ref "S5") (pin "3") (pinfunction "O_3") (pintype "passive"))
      (node (ref "S6") (pin "3") (pinfunction "O_3") (pintype "passive"))
      (node (ref "S7") (pin "3") (pinfunction "O_3") (pintype "passive"))
      (node (ref "S8") (pin "3") (pinfunction "O_3") (pintype "passive"))
      (node (ref "S9") (pin "3") (pinfunction "O_3") (pintype "passive"))
      (node (ref "U$1") (pin "1") (pinfunction "1_1") (pintype "bidirectional"))
      (node (ref "U$1") (pin "10") (pinfunction "L/R+_10") (pintype "bidirectional"))
      (node (ref "U$1") (pin "11") (pinfunction "CASE_11") (pintype "bidirectional"))
      (node (ref "U$1") (pin "12") (pinfunction "CASE_12") (pintype "bidirectional"))
      (node (ref "U$1") (pin "15") (pinfunction "CASE_15") (pintype "bidirectional"))
      (node (ref "U$1") (pin "16") (pinfunction "CASE_16") (pintype "bidirectional"))
      (node (ref "U$1") (pin "3") (pinfunction "3_3") (pintype "bidirectional"))
      (node (ref "U$1") (pin "7") (pinfunction "U/D-_7") (pintype "bidirectional"))
      (node (ref "U$2") (pin "1") (pinfunction "GND1_1") (pintype "bidirectional"))
      (node (ref "U$2") (pin "6") (pinfunction "GND2_6") (pintype "bidirectional"))
      (node (ref "U1") (pin "3") (pinfunction "GND_3") (pintype "passive"))
      (node (ref "V1") (pin "2") (pinfunction "S_2") (pintype "passive"))
      (node (ref "V2") (pin "2") (pinfunction "S_2") (pintype "passive"))
      (node (ref "V21") (pin "2") (pinfunction "S_2") (pintype "passive"))
      (node (ref "V3") (pin "2") (pinfunction "S_2") (pintype "passive"))
      (node (ref "V4") (pin "2") (pinfunction "S_2") (pintype "passive"))
      (node (ref "X1") (pin "10") (pinfunction "KL_10") (pintype "passive"))
      (node (ref "X2") (pin "1.1") (pinfunction "KL_1.1") (pintype "passive"))
      (node (ref "X2") (pin "1.2") (pinfunction "KL_1.2") (pintype "passive"))
      (node (ref "X3") (pin "12") (pinfunction "KL_12") (pintype "passive"))
      (node (ref "X3") (pin "6") (pinfunction "KL_6") (pintype "passive"))
      (node (ref "X4") (pin "10") (pinfunction "KL_10") (pintype "passive"))
      (node (ref "X5") (pin "10") (pinfunction "KL_10") (pintype "passive"))
    )
    (net (code "79") (name "Net-(+5V-POWER-PadA)") (class "Default")
      (node (ref "+5V-POWER") (pin "A") (pinfunction "A_A") (pintype "passive"))
      (node (ref "R11") (pin "1") (pinfunction "1_1") (pintype "passive"))
    )
    (net (code "80") (name "Net-(D1-PadA)") (class "Default")
      (node (ref "D1") (pin "A") (pinfunction "A_A") (pintype "passive"))
      (node (ref "R39") (pin "1") (pinfunction "1_1") (pintype "passive"))
    )
    (net (code "81") (name "Net-(D2-PadC)") (class "Default")
      (node (ref "D2") (pin "C") (pinfunction "C_C") (pintype "passive"))
      (node (ref "R40") (pin "1") (pinfunction "1_1") (pintype "passive"))
    )
    (net (code "82") (name "Net-(F1-Pad1)") (class "Default")
      (node (ref "F1") (pin "1") (pinfunction "1_1") (pintype "passive"))
      (node (ref "X2") (pin "2.1") (pinfunction "KL_2.1") (pintype "passive"))
      (node (ref "X2") (pin "2.2") (pinfunction "KL_2.2") (pintype "passive"))
    )
    (net (code "83") (name "Net-(F1-Pad2)") (class "Default")
      (node (ref "F1") (pin "2") (pinfunction "2_2") (pintype "passive"))
      (node (ref "JP1") (pin "1") (pinfunction "1_1") (pintype "passive"))
    )
    (net (code "84") (name "Net-(F2-Pad2)") (class "Default")
      (node (ref "F2") (pin "2") (pinfunction "2_2") (pintype "passive"))
      (node (ref "JP1") (pin "3") (pinfunction "3_3") (pintype "passive"))
    )
    (net (code "85") (name "Net-(H0-PadC)") (class "Default")
      (node (ref "H0") (pin "C") (pinfunction "C_C") (pintype "passive"))
      (node (ref "R36") (pin "2") (pinfunction "2_2") (pintype "passive"))
    )
    (net (code "86") (name "Net-(H1-PadC)") (class "Default")
      (node (ref "H1") (pin "C") (pinfunction "C_C") (pintype "passive"))
      (node (ref "R35") (pin "2") (pinfunction "2_2") (pintype "passive"))
    )
    (net (code "87") (name "Net-(H2-PadC)") (class "Default")
      (node (ref "H2") (pin "C") (pinfunction "C_C") (pintype "passive"))
      (node (ref "R34") (pin "2") (pinfunction "2_2") (pintype "passive"))
    )
    (net (code "88") (name "Net-(H3-PadC)") (class "Default")
      (node (ref "H3") (pin "C") (pinfunction "C_C") (pintype "passive"))
      (node (ref "R33") (pin "2") (pinfunction "2_2") (pintype "passive"))
    )
    (net (code "89") (name "Net-(H4-PadC)") (class "Default")
      (node (ref "H4") (pin "C") (pinfunction "C_C") (pintype "passive"))
      (node (ref "R32") (pin "2") (pinfunction "2_2") (pintype "passive"))
    )
    (net (code "90") (name "Net-(H5-PadC)") (class "Default")
      (node (ref "H5") (pin "C") (pinfunction "C_C") (pintype "passive"))
      (node (ref "R31") (pin "2") (pinfunction "2_2") (pintype "passive"))
    )
    (net (code "91") (name "Net-(H6-PadC)") (class "Default")
      (node (ref "H6") (pin "C") (pinfunction "C_C") (pintype "passive"))
      (node (ref "R30") (pin "2") (pinfunction "2_2") (pintype "passive"))
    )
    (net (code "92") (name "Net-(H7-PadC)") (class "Default")
      (node (ref "H7") (pin "C") (pinfunction "C_C") (pintype "passive"))
      (node (ref "R29") (pin "2") (pinfunction "2_2") (pintype "passive"))
    )
    (net (code "93") (name "Net-(H8-PadC)") (class "Default")
      (node (ref "H8") (pin "C") (pinfunction "C_C") (pintype "passive"))
      (node (ref "R24") (pin "2") (pinfunction "2_2") (pintype "passive"))
    )
    (net (code "94") (name "Net-(H9-PadC)") (class "Default")
      (node (ref "H9") (pin "C") (pinfunction "C_C") (pintype "passive"))
      (node (ref "R25") (pin "2") (pinfunction "2_2") (pintype "passive"))
    )
    (net (code "95") (name "Net-(H10-PadC)") (class "Default")
      (node (ref "H10") (pin "C") (pinfunction "C_C") (pintype "passive"))
      (node (ref "R22") (pin "2") (pinfunction "2_2") (pintype "passive"))
    )
    (net (code "96") (name "Net-(H11-PadC)") (class "Default")
      (node (ref "H11") (pin "C") (pinfunction "C_C") (pintype "passive"))
      (node (ref "R23") (pin "2") (pinfunction "2_2") (pintype "passive"))
    )
    (net (code "97") (name "Net-(H12-PadC)") (class "Default")
      (node (ref "H12") (pin "C") (pinfunction "C_C") (pintype "passive"))
      (node (ref "R20") (pin "2") (pinfunction "2_2") (pintype "passive"))
    )
    (net (code "98") (name "Net-(H13-PadC)") (class "Default")
      (node (ref "H13") (pin "C") (pinfunction "C_C") (pintype "passive"))
      (node (ref "R21") (pin "2") (pinfunction "2_2") (pintype "passive"))
    )
    (net (code "99") (name "Net-(H14-PadC)") (class "Default")
      (node (ref "H14") (pin "C") (pinfunction "C_C") (pintype "passive"))
      (node (ref "R18") (pin "2") (pinfunction "2_2") (pintype "passive"))
    )
    (net (code "100") (name "Net-(H15-PadC)") (class "Default")
      (node (ref "H15") (pin "C") (pinfunction "C_C") (pintype "passive"))
      (node (ref "R19") (pin "2") (pinfunction "2_2") (pintype "passive"))
    )
    (net (code "101") (name "Net-(IC1A-I)") (class "Default")
      (node (ref "C1") (pin "1") (pinfunction "1_1") (pintype "passive"))
      (node (ref "IC1") (pin "13") (pinfunction "I_13") (pintype "input"))
      (node (ref "R3") (pin "2") (pinfunction "2_2") (pintype "passive"))
      (node (ref "S1") (pin "1") (pinfunction "1_1") (pintype "passive"))
      (node (ref "S1") (pin "2") (pinfunction "2_2") (pintype "passive"))
    )
    (net (code "102") (name "Net-(IC1B-I)") (class "Default")
      (node (ref "C2") (pin "1") (pinfunction "1_1") (pintype "passive"))
      (node (ref "IC1") (pin "11") (pinfunction "I_11") (pintype "input"))
      (node (ref "R4") (pin "2") (pinfunction "2_2") (pintype "passive"))
      (node (ref "S2") (pin "1") (pinfunction "1_1") (pintype "passive"))
      (node (ref "S2") (pin "2") (pinfunction "2_2") (pintype "passive"))
    )
    (net (code "103") (name "Net-(IC1C-I)") (class "Default")
      (node (ref "C10") (pin "1") (pinfunction "1_1") (pintype "passive"))
      (node (ref "IC1") (pin "9") (pinfunction "I_9") (pintype "input"))
      (node (ref "R8") (pin "1") (pinfunction "1_1") (pintype "passive"))
      (node (ref "S3") (pin "3") (pinfunction "3_3") (pintype "passive"))
      (node (ref "S3") (pin "4") (pinfunction "4_4") (pintype "passive"))
    )
    (net (code "104") (name "Net-(IC1D-I)") (class "Default")
      (node (ref "C11") (pin "1") (pinfunction "1_1") (pintype "passive"))
      (node (ref "IC1") (pin "1") (pinfunction "I_1") (pintype "input"))
      (node (ref "R9") (pin "1") (pinfunction "1_1") (pintype "passive"))
      (node (ref "S4") (pin "3") (pinfunction "3_3") (pintype "passive"))
      (node (ref "S4") (pin "4") (pinfunction "4_4") (pintype "passive"))
    )
    (net (code "105") (name "Net-(IC1E-I)") (class "Default")
      (node (ref "C23") (pin "1") (pinfunction "1_1") (pintype "passive"))
      (node (ref "IC1") (pin "3") (pinfunction "I_3") (pintype "input"))
      (node (ref "R45") (pin "1") (pinfunction "1_1") (pintype "passive"))
      (node (ref "U$1") (pin "2") (pinfunction "2_2") (pintype "bidirectional"))
      (node (ref "U$1") (pin "4") (pinfunction "4_4") (pintype "bidirectional"))
    )
    (net (code "106") (name "Net-(IC1F-I)") (class "Default")
      (node (ref "C27") (pin "1") (pinfunction "1_1") (pintype "passive"))
      (node (ref "IC1") (pin "5") (pinfunction "I_5") (pintype "input"))
      (node (ref "R41") (pin "2") (pinfunction "S_2") (pintype "passive"))
    )
    (net (code "107") (name "Net-(IC1F-O)") (class "Default")
      (node (ref "D1") (pin "C") (pinfunction "C_C") (pintype "passive"))
      (node (ref "D2") (pin "A") (pinfunction "A_A") (pintype "passive"))
      (node (ref "IC1") (pin "6") (pinfunction "O_6") (pintype "output"))
      (node (ref "V21") (pin "1") (pinfunction "G_1") (pintype "passive"))
    )
    (net (code "108") (name "Net-(IC2-(OC3C{slash}INT5)PE5)") (class "Default")
      (node (ref "IC2") (pin "7") (pinfunction "(OC3C/INT5)PE5_7") (pintype "bidirectional"))
      (node (ref "LSP3") (pin "MP") (pinfunction "MP_MP") (pintype "passive"))
    )
    (net (code "109") (name "Net-(IC2-(TOSC1)PG4)") (class "Default")
      (node (ref "C17") (pin "1") (pinfunction "1_1") (pintype "passive"))
      (node (ref "IC2") (pin "29") (pinfunction "(TOSC1)PG4_29") (pintype "bidirectional"))
      (node (ref "Q2") (pin "1") (pinfunction "1_1") (pintype "passive"))
    )
    (net (code "110") (name "Net-(IC2-(TOSC2)PG3)") (class "Default")
      (node (ref "C18") (pin "1") (pinfunction "1_1") (pintype "passive"))
      (node (ref "IC2") (pin "28") (pinfunction "(TOSC2)PG3_28") (pintype "bidirectional"))
      (node (ref "Q2") (pin "2") (pinfunction "2_2") (pintype "passive"))
    )
    (net (code "111") (name "Net-(IC2-AREF)") (class "Default")
      (node (ref "C13") (pin "2") (pinfunction "2_2") (pintype "passive"))
      (node (ref "IC2") (pin "98") (pinfunction "AREF_98") (pintype "bidirectional"))
    )
    (net (code "112") (name "Net-(IC2-AVCC)") (class "Default")
      (node (ref "C3") (pin "2") (pinfunction "2_2") (pintype "passive"))
      (node (ref "IC2") (pin "100") (pinfunction "AVCC_100") (pintype "power_in"))
      (node (ref "L1") (pin "2") (pinfunction "2_2") (pintype "passive"))
    )
    (net (code "113") (name "Net-(IC2-XTAL1)") (class "Default")
      (node (ref "C9") (pin "1") (pinfunction "1_1") (pintype "passive"))
      (node (ref "IC2") (pin "34") (pinfunction "XTAL1_34") (pintype "input"))
      (node (ref "Q1") (pin "1") (pinfunction "1_1") (pintype "passive"))
    )
    (net (code "114") (name "Net-(IC2-XTAL2)") (class "Default")
      (node (ref "C8") (pin "2") (pinfunction "2_2") (pintype "passive"))
      (node (ref "IC2") (pin "33") (pinfunction "XTAL2_33") (pintype "output"))
      (node (ref "Q1") (pin "2") (pinfunction "2_2") (pintype "passive"))
    )
    (net (code "115") (name "Net-(IC5A-Y0)") (class "Default")
      (node (ref "IC5") (pin "15") (pinfunction "Y0_15") (pintype "output"))
      (node (ref "Q10") (pin "1") (pinfunction "G_1") (pintype "passive"))
    )
    (net (code "116") (name "Net-(IC5A-Y1)") (class "Default")
      (node (ref "IC5") (pin "14") (pinfunction "Y1_14") (pintype "output"))
      (node (ref "Q9") (pin "1") (pinfunction "G_1") (pintype "passive"))
    )
    (net (code "117") (name "Net-(IC5A-Y2)") (class "Default")
      (node (ref "IC5") (pin "13") (pinfunction "Y2_13") (pintype "output"))
      (node (ref "Q8") (pin "1") (pinfunction "G_1") (pintype "passive"))
    )
    (net (code "118") (name "Net-(IC5A-Y3)") (class "Default")
      (node (ref "IC5") (pin "12") (pinfunction "Y3_12") (pintype "output"))
      (node (ref "Q7") (pin "1") (pinfunction "G_1") (pintype "passive"))
    )
    (net (code "119") (name "Net-(IC5A-Y4)") (class "Default")
      (node (ref "IC5") (pin "11") (pinfunction "Y4_11") (pintype "output"))
      (node (ref "Q6") (pin "1") (pinfunction "G_1") (pintype "passive"))
    )
    (net (code "120") (name "Net-(IC5A-Y5)") (class "Default")
      (node (ref "IC5") (pin "10") (pinfunction "Y5_10") (pintype "output"))
      (node (ref "Q5") (pin "1") (pinfunction "G_1") (pintype "passive"))
    )
    (net (code "121") (name "Net-(IC5A-Y6)") (class "Default")
      (node (ref "IC5") (pin "9") (pinfunction "Y6_9") (pintype "output"))
      (node (ref "Q4") (pin "1") (pinfunction "G_1") (pintype "passive"))
    )
    (net (code "122") (name "Net-(IC5A-Y7)") (class "Default")
      (node (ref "IC5") (pin "7") (pinfunction "Y7_7") (pintype "output"))
      (node (ref "Q3") (pin "1") (pinfunction "G_1") (pintype "passive"))
    )
    (net (code "123") (name "Net-(IC6-NC{slash}FB)") (class "Default")
      (node (ref "C21") (pin "1") (pinfunction "1_1") (pintype "passive"))
      (node (ref "IC6") (pin "4") (pinfunction "NC/FB_4") (pintype "passive"))
    )
    (net (code "124") (name "Net-(LCD1-CONTR)") (class "Default")
      (node (ref "LCD1") (pin "3") (pinfunction "CONTR_3") (pintype "input"))
      (node (ref "R13") (pin "1") (pinfunction "A_1") (pintype "passive"))
    )
    (net (code "125") (name "Net-(LCD1-E(SCLK))") (class "Default")
      (node (ref "LCD1") (pin "6") (pinfunction "E(SCLK)_6") (pintype "input"))
      (node (ref "R12") (pin "1") (pinfunction "1_1") (pintype "passive"))
      (node (ref "R15") (pin "2") (pinfunction "2_2") (pintype "passive"))
    )
    (net (code "126") (name "Net-(LCD1-LED+)") (class "Default")
      (node (ref "LCD1") (pin "17") (pinfunction "LED+_17") (pintype "passive"))
      (node (ref "R17") (pin "1") (pinfunction "1_1") (pintype "passive"))
    )
    (net (code "127") (name "Net-(LCD1-LED-)") (class "Default")
      (node (ref "LCD1") (pin "18") (pinfunction "LED-_18") (pintype "passive"))
      (node (ref "V4") (pin "3") (pinfunction "D_3") (pintype "passive"))
    )
    (net (code "128") (name "Net-(LCD1-R{slash}W(SID))") (class "Default")
      (node (ref "LCD1") (pin "5") (pinfunction "R/W(SID)_5") (pintype "input"))
      (node (ref "R14") (pin "1") (pinfunction "1_1") (pintype "passive"))
      (node (ref "R16") (pin "2") (pinfunction "2_2") (pintype "passive"))
    )
    (net (code "129") (name "Net-(Q3-D)") (class "Default")
      (node (ref "Q3") (pin "3") (pinfunction "D_3") (pintype "passive"))
      (node (ref "X3") (pin "4") (pinfunction "KL_4") (pintype "passive"))
    )
    (net (code "130") (name "Net-(Q4-D)") (class "Default")
      (node (ref "Q4") (pin "3") (pinfunction "D_3") (pintype "passive"))
      (node (ref "X3") (pin "13") (pinfunction "KL_13") (pintype "passive"))
    )
    (net (code "131") (name "Net-(Q5-D)") (class "Default")
      (node (ref "Q5") (pin "3") (pinfunction "D_3") (pintype "passive"))
      (node (ref "X3") (pin "11") (pinfunction "KL_11") (pintype "passive"))
    )
    (net (code "132") (name "Net-(Q6-D)") (class "Default")
      (node (ref "Q6") (pin "3") (pinfunction "D_3") (pintype "passive"))
      (node (ref "X3") (pin "9") (pinfunction "KL_9") (pintype "passive"))
    )
    (net (code "133") (name "Net-(Q7-D)") (class "Default")
      (node (ref "Q7") (pin "3") (pinfunction "D_3") (pintype "passive"))
      (node (ref "X3") (pin "7") (pinfunction "KL_7") (pintype "passive"))
    )
    (net (code "134") (name "Net-(Q8-D)") (class "Default")
      (node (ref "Q8") (pin "3") (pinfunction "D_3") (pintype "passive"))
      (node (ref "X3") (pin "5") (pinfunction "KL_5") (pintype "passive"))
    )
    (net (code "135") (name "Net-(Q9-D)") (class "Default")
      (node (ref "Q9") (pin "3") (pinfunction "D_3") (pintype "passive"))
      (node (ref "X3") (pin "3") (pinfunction "KL_3") (pintype "passive"))
    )
    (net (code "136") (name "Net-(Q10-D)") (class "Default")
      (node (ref "Q10") (pin "3") (pinfunction "D_3") (pintype "passive"))
      (node (ref "X3") (pin "1") (pinfunction "KL_1") (pintype "passive"))
    )
    (net (code "137") (name "Net-(R27-A)") (class "Default")
      (node (ref "R26") (pin "2") (pinfunction "2_2") (pintype "passive"))
      (node (ref "R27") (pin "1") (pinfunction "A_1") (pintype "passive"))
      (node (ref "U$3") (pin "E") (pinfunction "E_E") (pintype "passive"))
    )
    (net (code "138") (name "Net-(R27-E)") (class "Default")
      (node (ref "R27") (pin "2") (pinfunction "S_2") (pintype "passive"))
      (node (ref "R27") (pin "3") (pinfunction "E_3") (pintype "passive"))
      (node (ref "R28") (pin "2") (pinfunction "2_2") (pintype "passive"))
    )
    (net (code "139") (name "Net-(R41-A)") (class "Default")
      (node (ref "R39") (pin "2") (pinfunction "2_2") (pintype "passive"))
      (node (ref "R41") (pin "1") (pinfunction "A_1") (pintype "passive"))
    )
    (net (code "140") (name "Net-(R41-E)") (class "Default")
      (node (ref "R40") (pin "2") (pinfunction "2_2") (pintype "passive"))
      (node (ref "R41") (pin "3") (pinfunction "E_3") (pintype "passive"))
    )
    (net (code "141") (name "Net-(RGB1A-C)") (class "Default")
      (node (ref "R7") (pin "2") (pinfunction "2_2") (pintype "passive"))
      (node (ref "RGB1") (pin "1") (pinfunction "C_1") (pintype "passive"))
    )
    (net (code "142") (name "Net-(RGB1B-C)") (class "Default")
      (node (ref "R5") (pin "2") (pinfunction "2_2") (pintype "passive"))
      (node (ref "RGB1") (pin "2") (pinfunction "C_2") (pintype "passive"))
    )
    (net (code "143") (name "Net-(RGB1C-C)") (class "Default")
      (node (ref "R2") (pin "2") (pinfunction "2_2") (pintype "passive"))
      (node (ref "RGB1") (pin "3") (pinfunction "C_3") (pintype "passive"))
    )
    (net (code "144") (name "Net-(U$2-CC1)") (class "Default")
      (node (ref "R38") (pin "2") (pinfunction "2_2") (pintype "passive"))
      (node (ref "U$2") (pin "3") (pinfunction "CC1_3") (pintype "bidirectional"))
    )
    (net (code "145") (name "Net-(U$2-CC2)") (class "Default")
      (node (ref "R37") (pin "2") (pinfunction "2_2") (pintype "passive"))
      (node (ref "U$2") (pin "4") (pinfunction "CC2_4") (pintype "bidirectional"))
    )
    (net (code "146") (name "Net-(U$2-VBUS1)") (class "Default")
      (node (ref "F2") (pin "1") (pinfunction "1_1") (pintype "passive"))
      (node (ref "U$2") (pin "2") (pinfunction "VBUS1_2") (pintype "bidirectional"))
      (node (ref "U$2") (pin "5") (pinfunction "VBUS2_5") (pintype "bidirectional"))
    )
    (net (code "147") (name "Net-(V1-D)") (class "Default")
      (node (ref "R2") (pin "1") (pinfunction "1_1") (pintype "passive"))
      (node (ref "V1") (pin "3") (pinfunction "D_3") (pintype "passive"))
    )
    (net (code "148") (name "Net-(V2-D)") (class "Default")
      (node (ref "R5") (pin "1") (pinfunction "1_1") (pintype "passive"))
      (node (ref "V2") (pin "3") (pinfunction "D_3") (pintype "passive"))
    )
    (net (code "149") (name "Net-(V3-D)") (class "Default")
      (node (ref "R7") (pin "1") (pinfunction "1_1") (pintype "passive"))
      (node (ref "V3") (pin "3") (pinfunction "D_3") (pintype "passive"))
    )
    (net (code "150") (name "Net-(V5-D)") (class "Default")
      (node (ref "R36") (pin "1") (pinfunction "1_1") (pintype "passive"))
      (node (ref "V5") (pin "3") (pinfunction "D_3") (pintype "passive"))
    )
    (net (code "151") (name "Net-(V6-D)") (class "Default")
      (node (ref "R35") (pin "1") (pinfunction "1_1") (pintype "passive"))
      (node (ref "V6") (pin "3") (pinfunction "D_3") (pintype "passive"))
    )
    (net (code "152") (name "Net-(V7-D)") (class "Default")
      (node (ref "R34") (pin "1") (pinfunction "1_1") (pintype "passive"))
      (node (ref "V7") (pin "3") (pinfunction "D_3") (pintype "passive"))
    )
    (net (code "153") (name "Net-(V8-D)") (class "Default")
      (node (ref "R33") (pin "1") (pinfunction "1_1") (pintype "passive"))
      (node (ref "V8") (pin "3") (pinfunction "D_3") (pintype "passive"))
    )
    (net (code "154") (name "Net-(V9-D)") (class "Default")
      (node (ref "R32") (pin "1") (pinfunction "1_1") (pintype "passive"))
      (node (ref "V9") (pin "3") (pinfunction "D_3") (pintype "passive"))
    )
    (net (code "155") (name "Net-(V10-D)") (class "Default")
      (node (ref "R31") (pin "1") (pinfunction "1_1") (pintype "passive"))
      (node (ref "V10") (pin "3") (pinfunction "D_3") (pintype "passive"))
    )
    (net (code "156") (name "Net-(V11-D)") (class "Default")
      (node (ref "R30") (pin "1") (pinfunction "1_1") (pintype "passive"))
      (node (ref "V11") (pin "3") (pinfunction "D_3") (pintype "passive"))
    )
    (net (code "157") (name "Net-(V12-D)") (class "Default")
      (node (ref "R29") (pin "1") (pinfunction "1_1") (pintype "passive"))
      (node (ref "V12") (pin "3") (pinfunction "D_3") (pintype "passive"))
    )
    (net (code "158") (name "Net-(V13-D)") (class "Default")
      (node (ref "R24") (pin "1") (pinfunction "1_1") (pintype "passive"))
      (node (ref "V13") (pin "3") (pinfunction "D_3") (pintype "passive"))
    )
    (net (code "159") (name "Net-(V14-D)") (class "Default")
      (node (ref "R25") (pin "1") (pinfunction "1_1") (pintype "passive"))
      (node (ref "V14") (pin "3") (pinfunction "D_3") (pintype "passive"))
    )
    (net (code "160") (name "Net-(V15-D)") (class "Default")
      (node (ref "R22") (pin "1") (pinfunction "1_1") (pintype "passive"))
      (node (ref "V15") (pin "3") (pinfunction "D_3") (pintype "passive"))
    )
    (net (code "161") (name "Net-(V16-D)") (class "Default")
      (node (ref "R23") (pin "1") (pinfunction "1_1") (pintype "passive"))
      (node (ref "V16") (pin "3") (pinfunction "D_3") (pintype "passive"))
    )
    (net (code "162") (name "Net-(V17-D)") (class "Default")
      (node (ref "R20") (pin "1") (pinfunction "1_1") (pintype "passive"))
      (node (ref "V17") (pin "3") (pinfunction "D_3") (pintype "passive"))
    )
    (net (code "163") (name "Net-(V18-D)") (class "Default")
      (node (ref "R21") (pin "1") (pinfunction "1_1") (pintype "passive"))
      (node (ref "V18") (pin "3") (pinfunction "D_3") (pintype "passive"))
    )
    (net (code "164") (name "Net-(V19-D)") (class "Default")
      (node (ref "R18") (pin "1") (pinfunction "1_1") (pintype "passive"))
      (node (ref "V19") (pin "3") (pinfunction "D_3") (pintype "passive"))
    )
    (net (code "165") (name "Net-(V20-D)") (class "Default")
      (node (ref "R19") (pin "1") (pinfunction "1_1") (pintype "passive"))
      (node (ref "V20") (pin "3") (pinfunction "D_3") (pintype "passive"))
    )
    (net (code "166") (name "VCC") (class "Default")
      (node (ref "C12") (pin "1") (pinfunction "1_1") (pintype "passive"))
      (node (ref "C14") (pin "+") (pinfunction "+_+") (pintype "passive"))
      (node (ref "C16") (pin "1") (pinfunction "1_1") (pintype "passive"))
      (node (ref "C20") (pin "1") (pinfunction "1_1") (pintype "passive"))
      (node (ref "C24") (pin "+") (pinfunction "+_+") (pintype "passive"))
      (node (ref "C25") (pin "+") (pinfunction "+_+") (pintype "passive"))
      (node (ref "C26") (pin "1") (pinfunction "1_1") (pintype "passive"))
      (node (ref "C4") (pin "1") (pinfunction "1_1") (pintype "passive"))
      (node (ref "C5") (pin "1") (pinfunction "1_1") (pintype "passive"))
      (node (ref "C6") (pin "1") (pinfunction "1_1") (pintype "passive"))
      (node (ref "C7") (pin "1") (pinfunction "1_1") (pintype "passive"))
      (node (ref "H0") (pin "A") (pinfunction "A_A") (pintype "passive"))
      (node (ref "H1") (pin "A") (pinfunction "A_A") (pintype "passive"))
      (node (ref "H10") (pin "A") (pinfunction "A_A") (pintype "passive"))
      (node (ref "H11") (pin "A") (pinfunction "A_A") (pintype "passive"))
      (node (ref "H12") (pin "A") (pinfunction "A_A") (pintype "passive"))
      (node (ref "H13") (pin "A") (pinfunction "A_A") (pintype "passive"))
      (node (ref "H14") (pin "A") (pinfunction "A_A") (pintype "passive"))
      (node (ref "H15") (pin "A") (pinfunction "A_A") (pintype "passive"))
      (node (ref "H2") (pin "A") (pinfunction "A_A") (pintype "passive"))
      (node (ref "H3") (pin "A") (pinfunction "A_A") (pintype "passive"))
      (node (ref "H4") (pin "A") (pinfunction "A_A") (pintype "passive"))
      (node (ref "H5") (pin "A") (pinfunction "A_A") (pintype "passive"))
      (node (ref "H6") (pin "A") (pinfunction "A_A") (pintype "passive"))
      (node (ref "H7") (pin "A") (pinfunction "A_A") (pintype "passive"))
      (node (ref "H8") (pin "A") (pinfunction "A_A") (pintype "passive"))
      (node (ref "H9") (pin "A") (pinfunction "A_A") (pintype "passive"))
      (node (ref "IC1") (pin "14") (pinfunction "VCC_14") (pintype "power_in"))
      (node (ref "IC2") (pin "10") (pinfunction "VCC_10") (pintype "power_in"))
      (node (ref "IC2") (pin "31") (pinfunction "VCC1_31") (pintype "power_in"))
      (node (ref "IC2") (pin "61") (pinfunction "VCC2_61") (pintype "power_in"))
      (node (ref "IC2") (pin "80") (pinfunction "VCC3_80") (pintype "power_in"))
      (node (ref "IC3") (pin "1") (pinfunction "VCC_1") (pintype "power_in"))
      (node (ref "IC4") (pin "1") (pinfunction "VCC_1") (pintype "power_in"))
      (node (ref "IC5") (pin "16") (pinfunction "VCC_16") (pintype "power_in"))
      (node (ref "IC6") (pin "1") (pinfunction "IN_1") (pintype "input"))
      (node (ref "IC6") (pin "3") (pinfunction "ON/~{OFF}_3") (pintype "input"))
      (node (ref "JP1") (pin "2") (pinfunction "2_2") (pintype "passive"))
      (node (ref "JP2") (pin "2") (pinfunction "2_2") (pintype "passive"))
      (node (ref "JP3") (pin "2") (pinfunction "2_2") (pintype "passive"))
      (node (ref "JTAG") (pin "4") (pinfunction "4_4") (pintype "passive"))
      (node (ref "L1") (pin "1") (pinfunction "1_1") (pintype "passive"))
      (node (ref "Q10") (pin "2") (pinfunction "S_2") (pintype "passive"))
      (node (ref "Q3") (pin "2") (pinfunction "S_2") (pintype "passive"))
      (node (ref "Q4") (pin "2") (pinfunction "S_2") (pintype "passive"))
      (node (ref "Q5") (pin "2") (pinfunction "S_2") (pintype "passive"))
      (node (ref "Q6") (pin "2") (pinfunction "S_2") (pintype "passive"))
      (node (ref "Q7") (pin "2") (pinfunction "S_2") (pintype "passive"))
      (node (ref "Q8") (pin "2") (pinfunction "S_2") (pintype "passive"))
      (node (ref "Q9") (pin "2") (pinfunction "S_2") (pintype "passive"))
      (node (ref "R1") (pin "3") (pinfunction "E_3") (pintype "passive"))
      (node (ref "R10") (pin "2") (pinfunction "2_2") (pintype "passive"))
      (node (ref "R11") (pin "2") (pinfunction "2_2") (pintype "passive"))
      (node (ref "R17") (pin "2") (pinfunction "2_2") (pintype "passive"))
      (node (ref "R3") (pin "1") (pinfunction "1_1") (pintype "passive"))
      (node (ref "R4") (pin "1") (pinfunction "1_1") (pintype "passive"))
      (node (ref "R45") (pin "2") (pinfunction "2_2") (pintype "passive"))
      (node (ref "R6") (pin "3") (pinfunction "E_3") (pintype "passive"))
      (node (ref "R8") (pin "2") (pinfunction "2_2") (pintype "passive"))
      (node (ref "R9") (pin "2") (pinfunction "2_2") (pintype "passive"))
      (node (ref "RGB1") (pin "4") (pinfunction "A_4") (pintype "passive"))
      (node (ref "RGB1") (pin "5") (pinfunction "A_5") (pintype "passive"))
      (node (ref "RGB1") (pin "6") (pinfunction "A_6") (pintype "passive"))
      (node (ref "S10") (pin "1") (pinfunction "S_1") (pintype "passive"))
      (node (ref "S11") (pin "1") (pinfunction "S_1") (pintype "passive"))
      (node (ref "S12") (pin "1") (pinfunction "S_1") (pintype "passive"))
      (node (ref "S5") (pin "1") (pinfunction "S_1") (pintype "passive"))
      (node (ref "S6") (pin "1") (pinfunction "S_1") (pintype "passive"))
      (node (ref "S7") (pin "1") (pinfunction "S_1") (pintype "passive"))
      (node (ref "S8") (pin "1") (pinfunction "S_1") (pintype "passive"))
      (node (ref "S9") (pin "1") (pinfunction "S_1") (pintype "passive"))
      (node (ref "U$1") (pin "5") (pinfunction "U/D+_5") (pintype "bidirectional"))
      (node (ref "U$1") (pin "8") (pinfunction "L/R-_8") (pintype "bidirectional"))
      (node (ref "U$3") (pin "C") (pinfunction "C_C") (pintype "passive"))
      (node (ref "U1") (pin "1") (pinfunction "+VS_1") (pintype "passive"))
      (node (ref "X1") (pin "9") (pinfunction "KL_9") (pintype "passive"))
      (node (ref "X3") (pin "14") (pinfunction "KL_14") (pintype "passive"))
      (node (ref "X4") (pin "9") (pinfunction "KL_9") (pintype "passive"))
      (node (ref "X5") (pin "9") (pinfunction "KL_9") (pintype "passive"))
    )
    (net (code "167") (name "unconnected-(IC2-(ALE)PG2-Pad70)") (class "Default")
      (node (ref "IC2") (pin "70") (pinfunction "(ALE)PG2_70") (pintype "bidirectional"))
    )
    (net (code "168") (name "unconnected-(IC2-(CLKO{slash}ICP3{slash}INT7)PE7-Pad9)") (class "Default")
      (node (ref "IC2") (pin "9") (pinfunction "(CLKO/ICP3/INT7)PE7_9") (pintype "bidirectional"))
    )
    (net (code "169") (name "unconnected-(IC2-(T3{slash}INT6)PE6-Pad8)") (class "Default")
      (node (ref "IC2") (pin "8") (pinfunction "(T3/INT6)PE6_8") (pintype "bidirectional"))
    )
    (net (code "170") (name "unconnected-(IC2-PH0(RXD2)-Pad12)") (class "Default")
      (node (ref "IC2") (pin "12") (pinfunction "PH0(RXD2)_12") (pintype "bidirectional"))
    )
    (net (code "171") (name "unconnected-(IC2-PH1(TXD2)-Pad13)") (class "Default")
      (node (ref "IC2") (pin "13") (pinfunction "PH1(TXD2)_13") (pintype "bidirectional"))
    )
    (net (code "172") (name "unconnected-(IC2-PH2(XCK2)-Pad14)") (class "Default")
      (node (ref "IC2") (pin "14") (pinfunction "PH2(XCK2)_14") (pintype "bidirectional"))
    )
    (net (code "173") (name "unconnected-(IC2-PH6(OC2B)-Pad18)") (class "Default")
      (node (ref "IC2") (pin "18") (pinfunction "PH6(OC2B)_18") (pintype "bidirectional"))
    )
    (net (code "174") (name "unconnected-(IC2-PH7(T4)-Pad27)") (class "Default")
      (node (ref "IC2") (pin "27") (pinfunction "PH7(T4)_27") (pintype "bidirectional"))
    )
    (net (code "175") (name "unconnected-(IC2-PJ7-Pad79)") (class "Default")
      (node (ref "IC2") (pin "79") (pinfunction "PJ7_79") (pintype "bidirectional"))
    )
    (net (code "176") (name "unconnected-(LCD1-D0(SOD)-Pad7)") (class "Default")
      (node (ref "LCD1") (pin "7") (pinfunction "D0(SOD)_7") (pintype "no_connect"))
    )
    (net (code "177") (name "unconnected-(LCD1-D1-Pad8)") (class "Default")
      (node (ref "LCD1") (pin "8") (pinfunction "D1_8") (pintype "no_connect"))
    )
    (net (code "178") (name "unconnected-(LCD1-D2-Pad9)") (class "Default")
      (node (ref "LCD1") (pin "9") (pinfunction "D2_9") (pintype "no_connect"))
    )
    (net (code "179") (name "unconnected-(LCD1-D3-Pad10)") (class "Default")
      (node (ref "LCD1") (pin "10") (pinfunction "D3_10") (pintype "no_connect"))
    )
    (net (code "180") (name "unconnected-(LCD1-D4-Pad11)") (class "Default")
      (node (ref "LCD1") (pin "11") (pinfunction "D4_11") (pintype "no_connect"))
    )
    (net (code "181") (name "unconnected-(LCD1-D5-Pad12)") (class "Default")
      (node (ref "LCD1") (pin "12") (pinfunction "D5_12") (pintype "no_connect"))
    )
    (net (code "182") (name "unconnected-(LCD1-D6-Pad13)") (class "Default")
      (node (ref "LCD1") (pin "13") (pinfunction "D6_13") (pintype "no_connect"))
    )
    (net (code "183") (name "unconnected-(LCD1-D7-Pad14)") (class "Default")
      (node (ref "LCD1") (pin "14") (pinfunction "D7_14") (pintype "no_connect"))
    )
    (net (code "184") (name "unconnected-(LCD1-NC-Pad15)") (class "Default")
      (node (ref "LCD1") (pin "15") (pinfunction "NC_15") (pintype "no_connect"))
    )
    (net (code "185") (name "unconnected-(LCD1-RESET-Pad16)") (class "Default")
      (node (ref "LCD1") (pin "16") (pinfunction "RESET_16") (pintype "no_connect"))
    )
  )
)
